# serv_open8_sotb.net
KiCad netlist of a schematic drawn in EAGLE
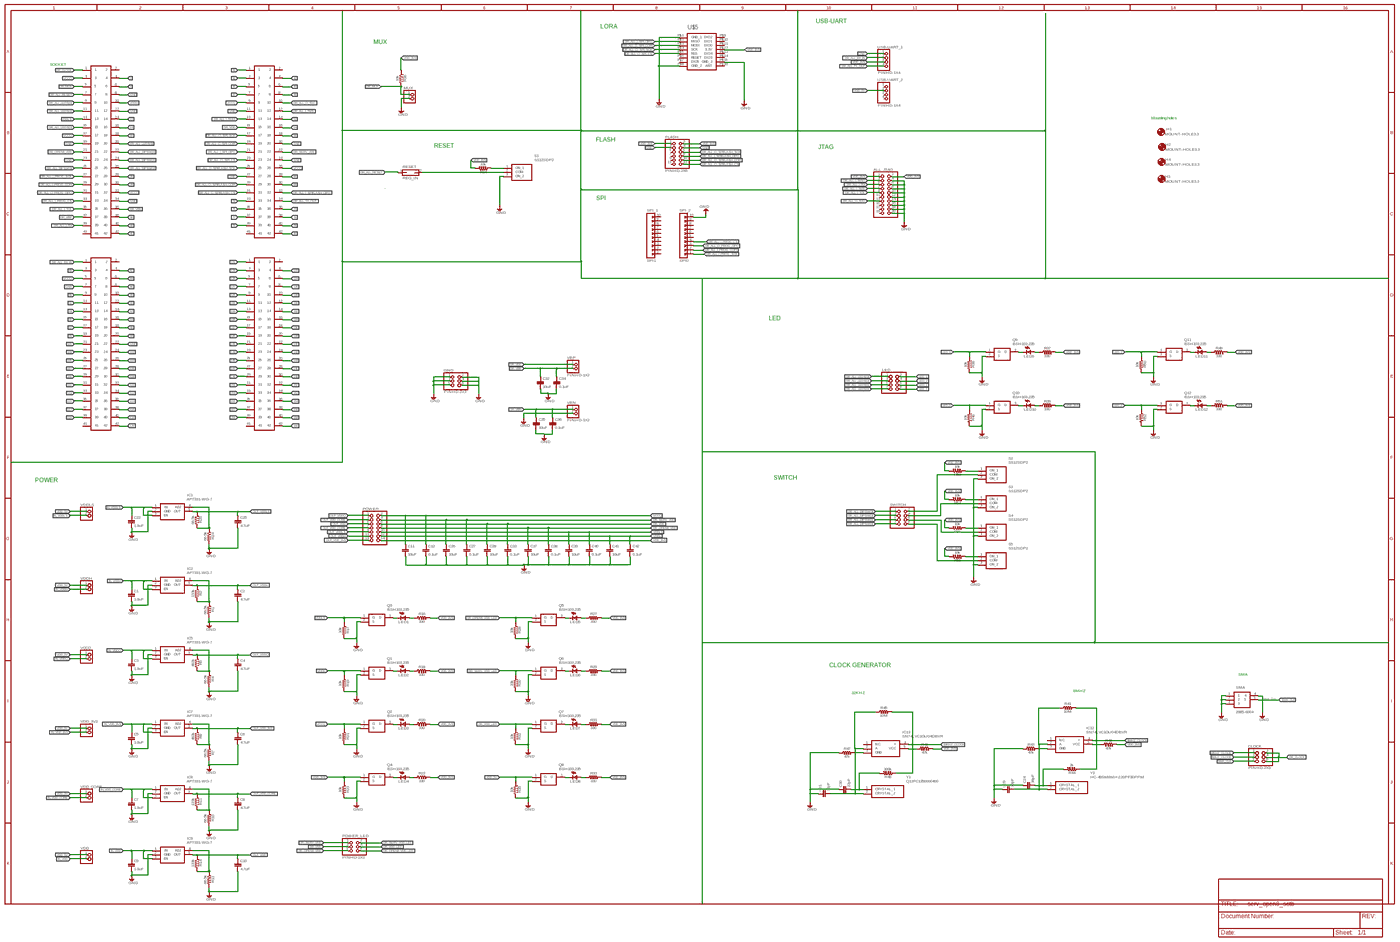
[diagram p0: schematic, sheet 1, overview]
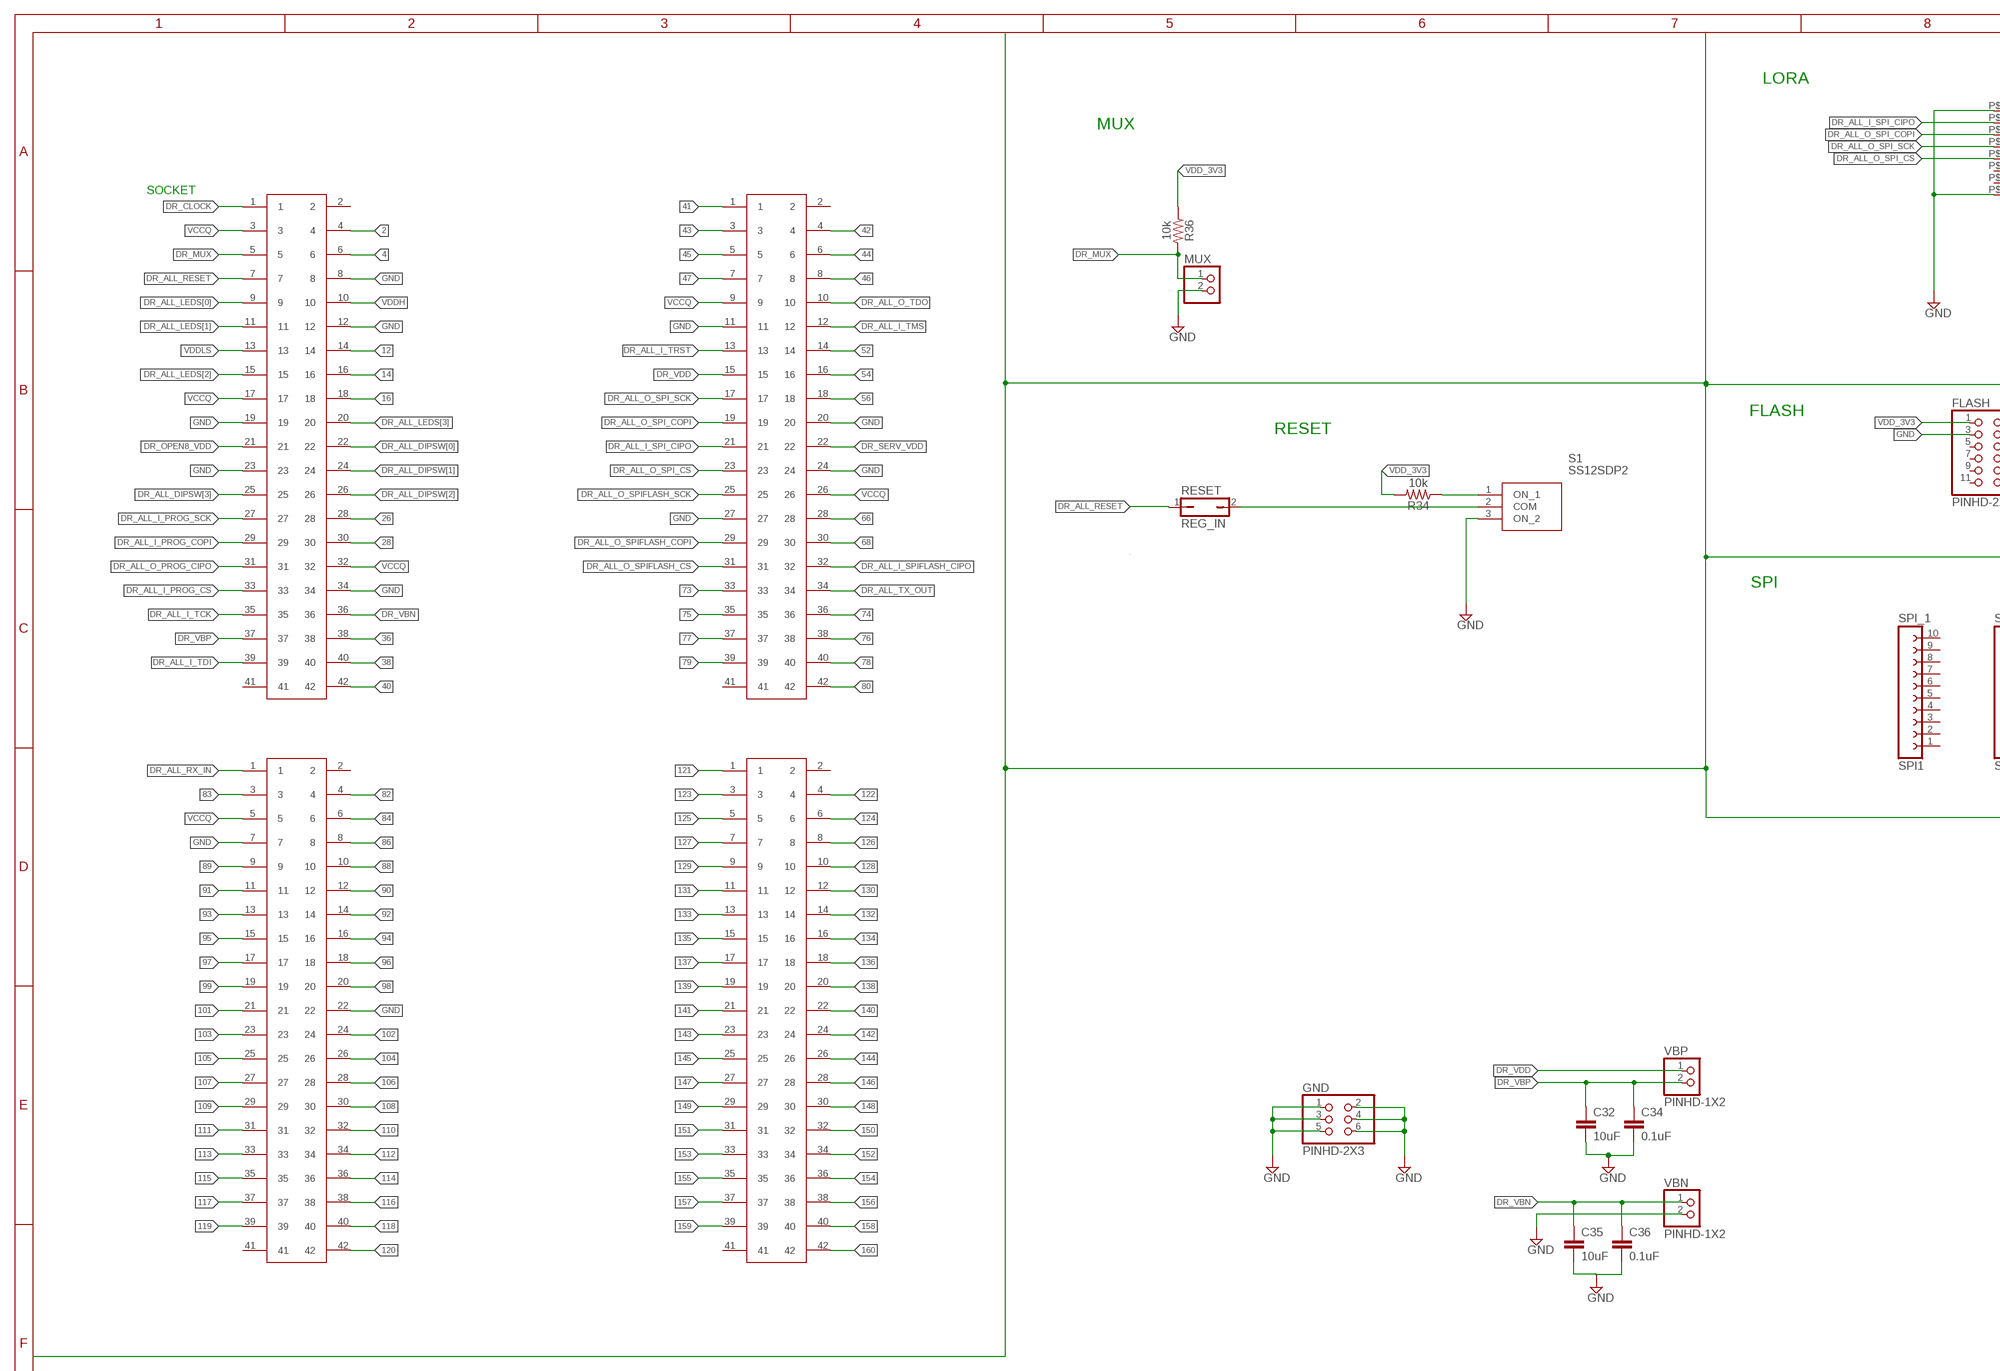
[diagram p1: schematic, sheet 1, part 1 of 4]
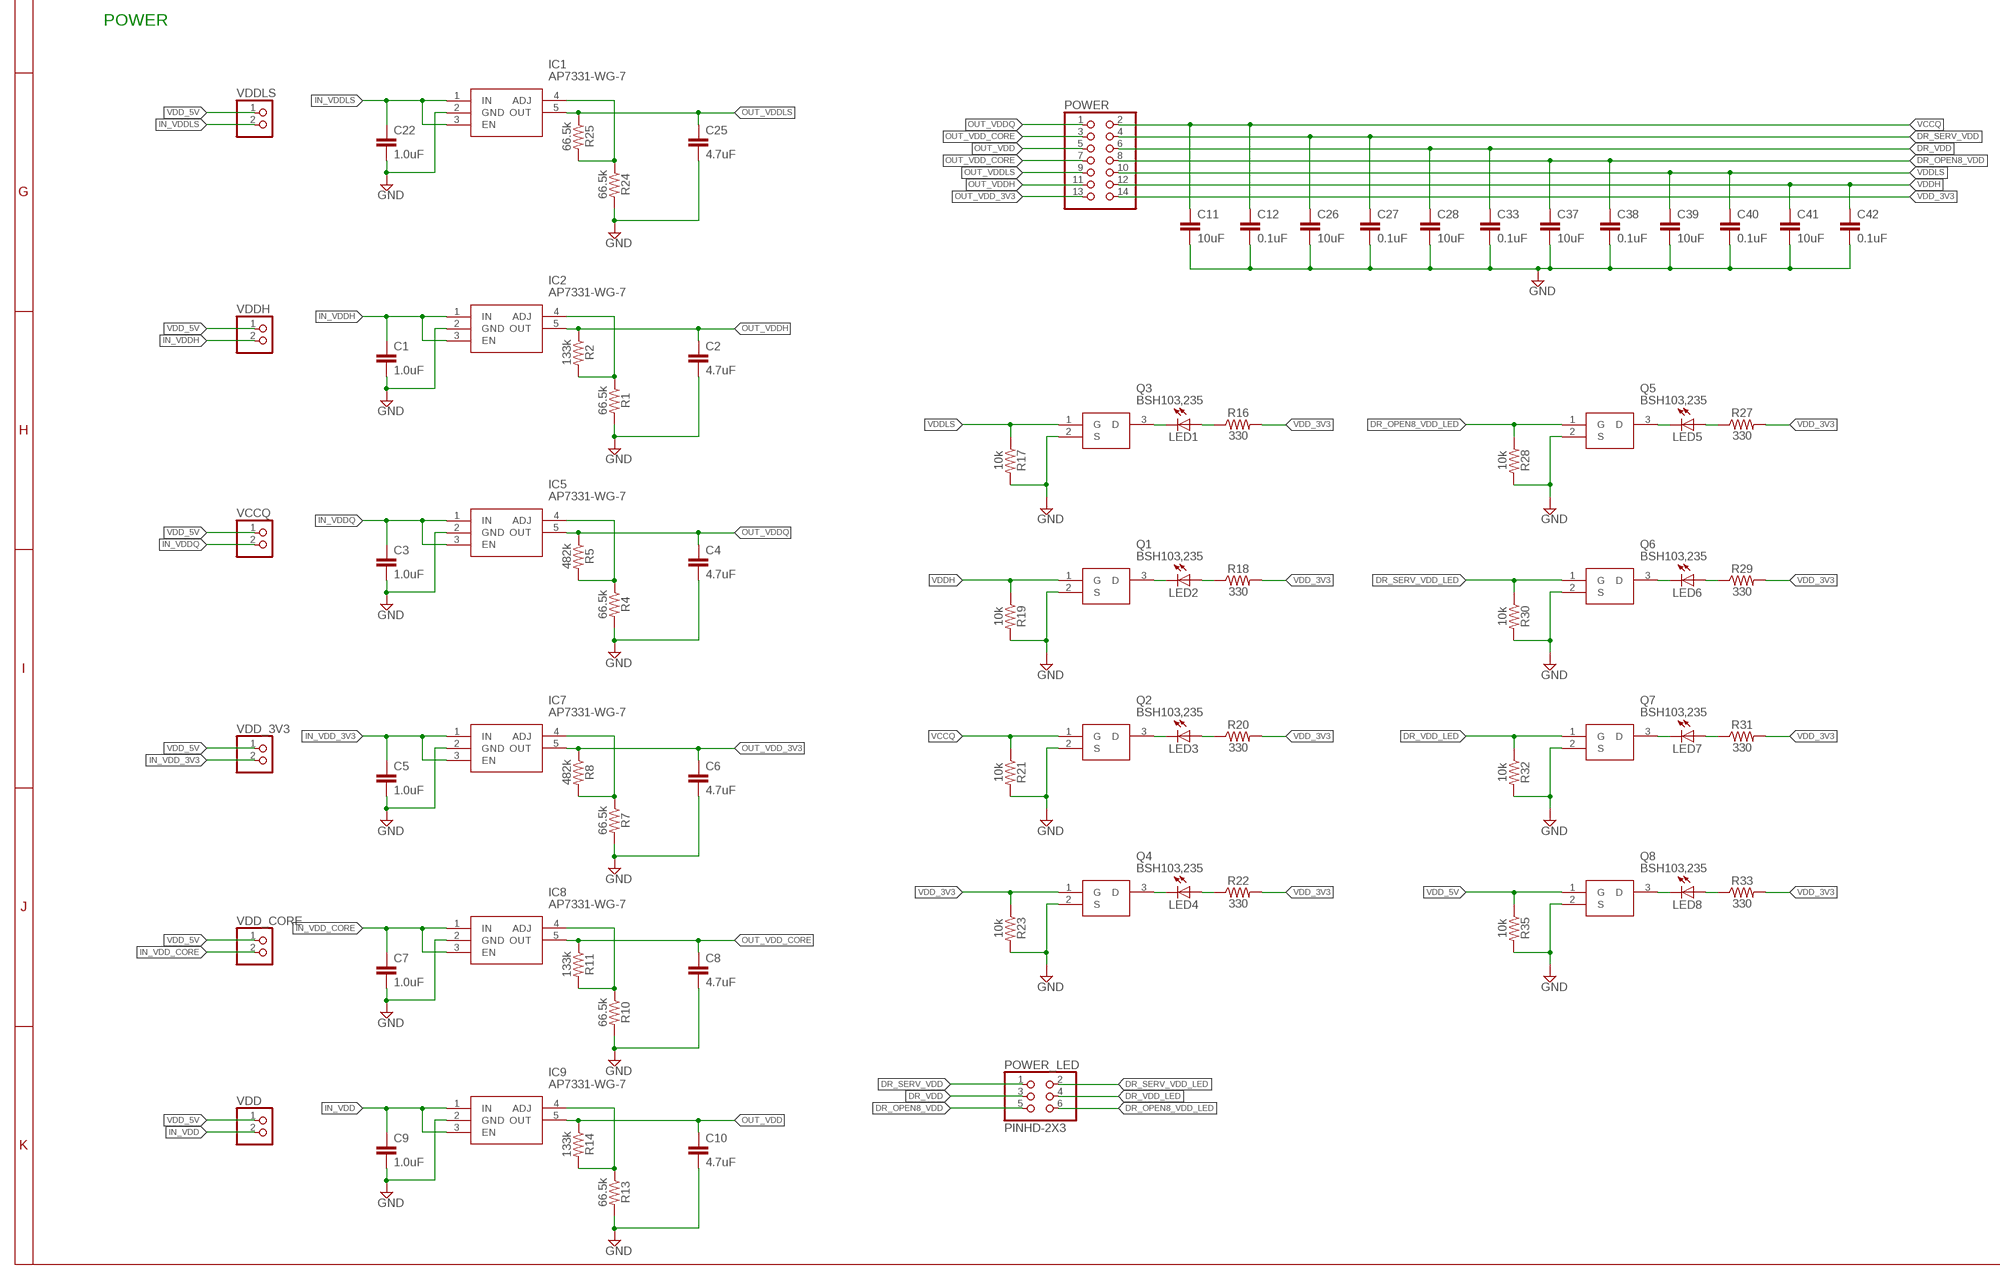
[diagram p2: schematic, sheet 1, part 2 of 4]
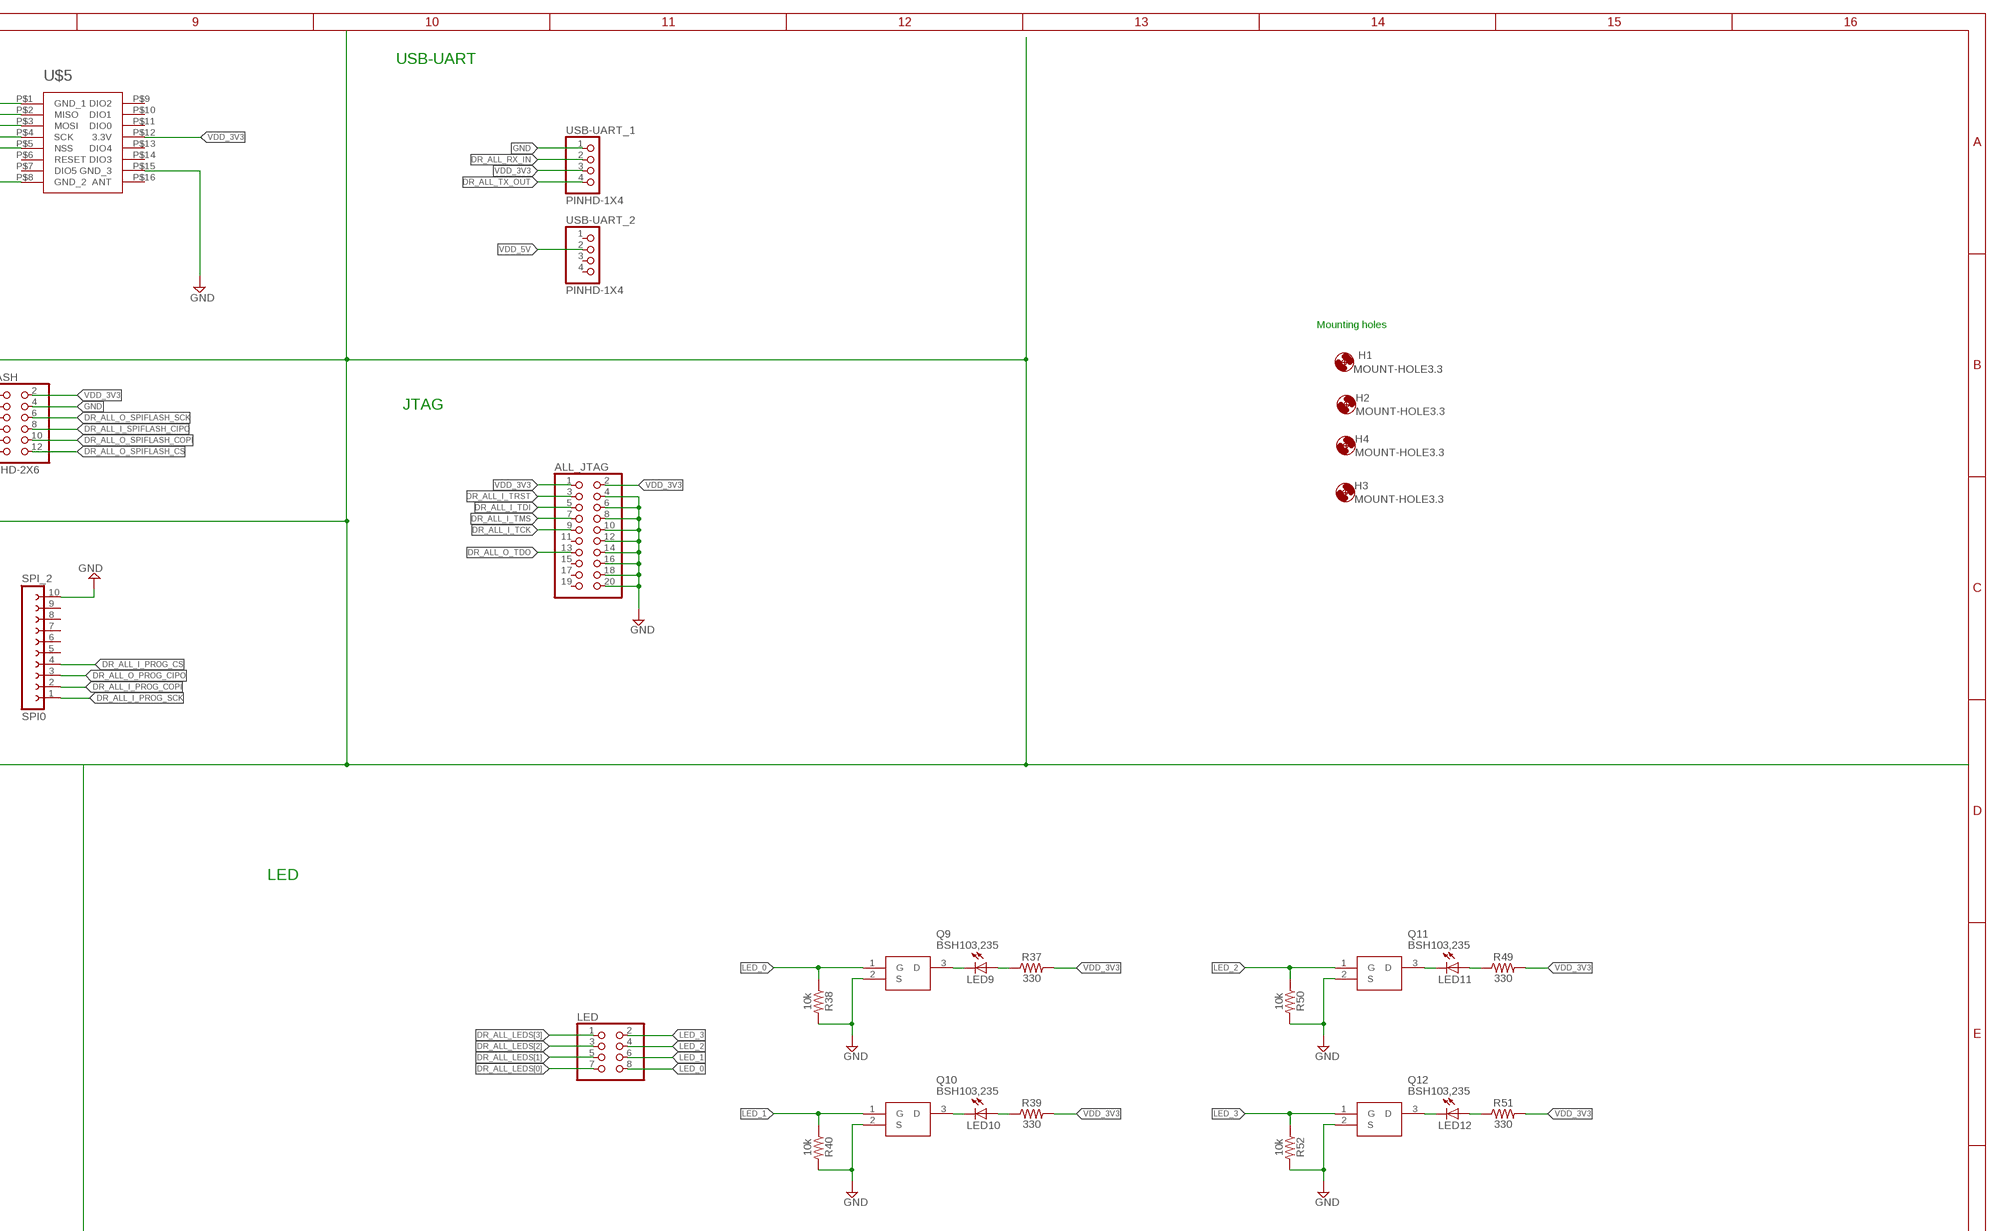
[diagram p3: schematic, sheet 1, part 3 of 4]
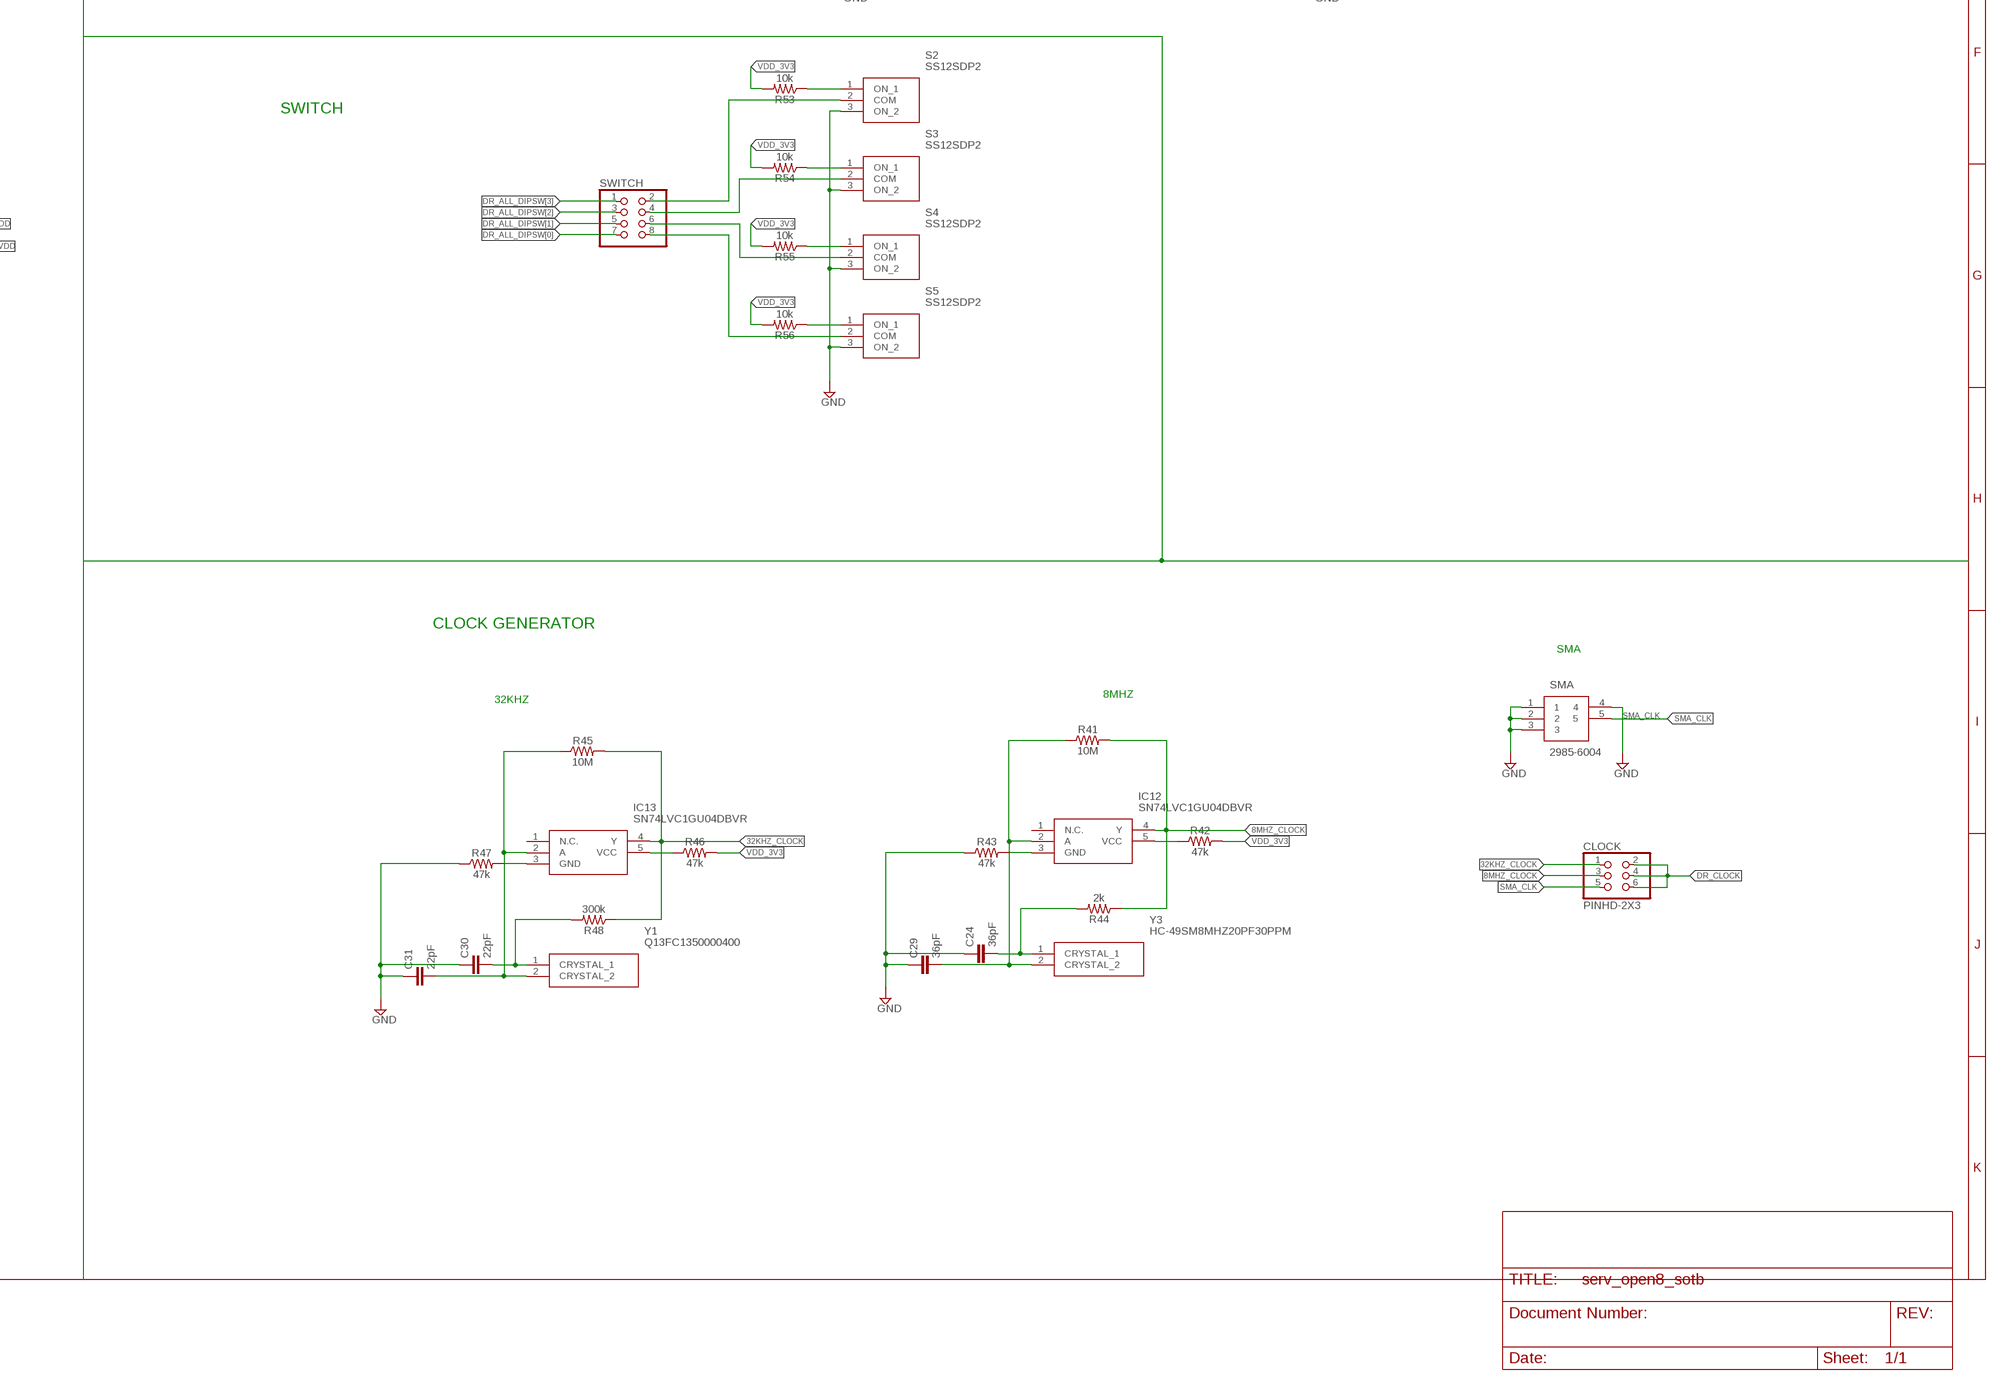
[diagram p4: schematic, sheet 1, part 4 of 4]

(export (version "E")
  (design (tool "Eeschema 10.0.6"))
  (components
    (comp (ref "ALL_JTAG")
      (value "PINHD-2X10")
      (footprint "eagle-import:2X10")
      (libsource (lib "eagle-import") (part "PINHD-2X10"))
    )
    (comp (ref "C1")
      (value "1.0uF")
      (footprint "eagle-import:0805")
      (libsource (lib "eagle-import") (part "1.0UF-0805-25V-(+80/-20%)"))
    )
    (comp (ref "C2")
      (value "4.7uF")
      (footprint "eagle-import:0805")
      (libsource (lib "eagle-import") (part "1.0UF-0805-25V-(+80/-20%)"))
    )
    (comp (ref "C3")
      (value "1.0uF")
      (footprint "eagle-import:0805")
      (libsource (lib "eagle-import") (part "1.0UF-0805-25V-(+80/-20%)"))
    )
    (comp (ref "C4")
      (value "4.7uF")
      (footprint "eagle-import:0805")
      (libsource (lib "eagle-import") (part "1.0UF-0805-25V-(+80/-20%)"))
    )
    (comp (ref "C5")
      (value "1.0uF")
      (footprint "eagle-import:0805")
      (libsource (lib "eagle-import") (part "1.0UF-0805-25V-(+80/-20%)"))
    )
    (comp (ref "C6")
      (value "4.7uF")
      (footprint "eagle-import:0805")
      (libsource (lib "eagle-import") (part "1.0UF-0805-25V-(+80/-20%)"))
    )
    (comp (ref "C7")
      (value "1.0uF")
      (footprint "eagle-import:0805")
      (libsource (lib "eagle-import") (part "1.0UF-0805-25V-(+80/-20%)"))
    )
    (comp (ref "C8")
      (value "4.7uF")
      (footprint "eagle-import:0805")
      (libsource (lib "eagle-import") (part "1.0UF-0805-25V-(+80/-20%)"))
    )
    (comp (ref "C9")
      (value "1.0uF")
      (footprint "eagle-import:0805")
      (libsource (lib "eagle-import") (part "1.0UF-0805-25V-(+80/-20%)"))
    )
    (comp (ref "C10")
      (value "4.7uF")
      (footprint "eagle-import:0805")
      (libsource (lib "eagle-import") (part "1.0UF-0805-25V-(+80/-20%)"))
    )
    (comp (ref "C11")
      (value "10uF")
      (footprint "eagle-import:0805")
      (libsource (lib "eagle-import") (part "1.0UF-0805-25V-(+80/-20%)"))
    )
    (comp (ref "C12")
      (value "0.1uF")
      (footprint "eagle-import:0805")
      (libsource (lib "eagle-import") (part "1.0UF-0805-25V-(+80/-20%)"))
    )
    (comp (ref "C22")
      (value "1.0uF")
      (footprint "eagle-import:0805")
      (libsource (lib "eagle-import") (part "1.0UF-0805-25V-(+80/-20%)"))
    )
    (comp (ref "C24")
      (value "36pF")
      (footprint "eagle-import:0805")
      (libsource (lib "eagle-import") (part "1.0UF-0805-25V-(+80/-20%)"))
    )
    (comp (ref "C25")
      (value "4.7uF")
      (footprint "eagle-import:0805")
      (libsource (lib "eagle-import") (part "1.0UF-0805-25V-(+80/-20%)"))
    )
    (comp (ref "C26")
      (value "10uF")
      (footprint "eagle-import:0805")
      (libsource (lib "eagle-import") (part "1.0UF-0805-25V-(+80/-20%)"))
    )
    (comp (ref "C27")
      (value "0.1uF")
      (footprint "eagle-import:0805")
      (libsource (lib "eagle-import") (part "1.0UF-0805-25V-(+80/-20%)"))
    )
    (comp (ref "C28")
      (value "10uF")
      (footprint "eagle-import:0805")
      (libsource (lib "eagle-import") (part "1.0UF-0805-25V-(+80/-20%)"))
    )
    (comp (ref "C29")
      (value "36pF")
      (footprint "eagle-import:0805")
      (libsource (lib "eagle-import") (part "1.0UF-0805-25V-(+80/-20%)"))
    )
    (comp (ref "C30")
      (value "22pF")
      (footprint "eagle-import:0805")
      (libsource (lib "eagle-import") (part "1.0UF-0805-25V-(+80/-20%)"))
    )
    (comp (ref "C31")
      (value "22pF")
      (footprint "eagle-import:0805")
      (libsource (lib "eagle-import") (part "1.0UF-0805-25V-(+80/-20%)"))
    )
    (comp (ref "C32")
      (value "10uF")
      (footprint "eagle-import:0805")
      (libsource (lib "eagle-import") (part "1.0UF-0805-25V-(+80/-20%)"))
    )
    (comp (ref "C33")
      (value "0.1uF")
      (footprint "eagle-import:0805")
      (libsource (lib "eagle-import") (part "1.0UF-0805-25V-(+80/-20%)"))
    )
    (comp (ref "C34")
      (value "0.1uF")
      (footprint "eagle-import:0805")
      (libsource (lib "eagle-import") (part "1.0UF-0805-25V-(+80/-20%)"))
    )
    (comp (ref "C35")
      (value "10uF")
      (footprint "eagle-import:0805")
      (libsource (lib "eagle-import") (part "1.0UF-0805-25V-(+80/-20%)"))
    )
    (comp (ref "C36")
      (value "0.1uF")
      (footprint "eagle-import:0805")
      (libsource (lib "eagle-import") (part "1.0UF-0805-25V-(+80/-20%)"))
    )
    (comp (ref "C37")
      (value "10uF")
      (footprint "eagle-import:0805")
      (libsource (lib "eagle-import") (part "1.0UF-0805-25V-(+80/-20%)"))
    )
    (comp (ref "C38")
      (value "0.1uF")
      (footprint "eagle-import:0805")
      (libsource (lib "eagle-import") (part "1.0UF-0805-25V-(+80/-20%)"))
    )
    (comp (ref "C39")
      (value "10uF")
      (footprint "eagle-import:0805")
      (libsource (lib "eagle-import") (part "1.0UF-0805-25V-(+80/-20%)"))
    )
    (comp (ref "C40")
      (value "0.1uF")
      (footprint "eagle-import:0805")
      (libsource (lib "eagle-import") (part "1.0UF-0805-25V-(+80/-20%)"))
    )
    (comp (ref "C41")
      (value "10uF")
      (footprint "eagle-import:0805")
      (libsource (lib "eagle-import") (part "1.0UF-0805-25V-(+80/-20%)"))
    )
    (comp (ref "C42")
      (value "0.1uF")
      (footprint "eagle-import:0805")
      (libsource (lib "eagle-import") (part "1.0UF-0805-25V-(+80/-20%)"))
    )
    (comp (ref "CLOCK")
      (value "PINHD-2X3")
      (footprint "eagle-import:2X03")
      (libsource (lib "eagle-import") (part "PINHD-2X3"))
    )
    (comp (ref "FLASH")
      (value "PINHD-2X6")
      (footprint "eagle-import:2X06")
      (libsource (lib "eagle-import") (part "PINHD-2X6"))
    )
    (comp (ref "GND")
      (value "PINHD-2X3")
      (footprint "eagle-import:2X03")
      (libsource (lib "eagle-import") (part "PINHD-2X3"))
    )
    (comp (ref "H1")
      (value "MOUNT-HOLE3.3")
      (footprint "eagle-import:3,3")
      (libsource (lib "eagle-import") (part "MOUNT-HOLE3.3"))
    )
    (comp (ref "H2")
      (value "MOUNT-HOLE3.3")
      (footprint "eagle-import:3,3")
      (libsource (lib "eagle-import") (part "MOUNT-HOLE3.3"))
    )
    (comp (ref "H3")
      (value "MOUNT-HOLE3.3")
      (footprint "eagle-import:3,3")
      (libsource (lib "eagle-import") (part "MOUNT-HOLE3.3"))
    )
    (comp (ref "H4")
      (value "MOUNT-HOLE3.3")
      (footprint "eagle-import:3,3")
      (libsource (lib "eagle-import") (part "MOUNT-HOLE3.3"))
    )
    (comp (ref "IC1")
      (value "AP7331-WG-7")
      (footprint "eagle-import:SOT95P285X145-5N")
      (fields (field (name "MOUSER_PART_NUMBER") "621-AP7331-WG-7"))
      (libsource (lib "eagle-import") (part "AP7331-WG-7"))
    )
    (comp (ref "IC2")
      (value "AP7331-WG-7")
      (footprint "eagle-import:SOT95P285X145-5N")
      (fields (field (name "MOUSER_PART_NUMBER") "621-AP7331-WG-7"))
      (libsource (lib "eagle-import") (part "AP7331-WG-7"))
    )
    (comp (ref "IC5")
      (value "AP7331-WG-7")
      (footprint "eagle-import:SOT95P285X145-5N")
      (fields (field (name "MOUSER_PART_NUMBER") "621-AP7331-WG-7"))
      (libsource (lib "eagle-import") (part "AP7331-WG-7"))
    )
    (comp (ref "IC7")
      (value "AP7331-WG-7")
      (footprint "eagle-import:SOT95P285X145-5N")
      (fields (field (name "MOUSER_PART_NUMBER") "621-AP7331-WG-7"))
      (libsource (lib "eagle-import") (part "AP7331-WG-7"))
    )
    (comp (ref "IC8")
      (value "AP7331-WG-7")
      (footprint "eagle-import:SOT95P285X145-5N")
      (fields (field (name "MOUSER_PART_NUMBER") "621-AP7331-WG-7"))
      (libsource (lib "eagle-import") (part "AP7331-WG-7"))
    )
    (comp (ref "IC9")
      (value "AP7331-WG-7")
      (footprint "eagle-import:SOT95P285X145-5N")
      (fields (field (name "MOUSER_PART_NUMBER") "621-AP7331-WG-7"))
      (libsource (lib "eagle-import") (part "AP7331-WG-7"))
    )
    (comp (ref "IC12")
      (value "SN74LVC1GU04DBVR")
      (footprint "eagle-import:SOT95P280X145-5N")
      (fields (field (name "MOUSER_PART_NUMBER") "595-SN74LVC1GU04DBVR"))
      (libsource (lib "eagle-import") (part "SN74LVC1GU04DBVR"))
    )
    (comp (ref "IC13")
      (value "SN74LVC1GU04DBVR")
      (footprint "eagle-import:SOT95P280X145-5N")
      (fields (field (name "MOUSER_PART_NUMBER") "595-SN74LVC1GU04DBVR"))
      (libsource (lib "eagle-import") (part "SN74LVC1GU04DBVR"))
    )
    (comp (ref "LED")
      (value "PINHD-2X4")
      (footprint "eagle-import:2X04")
      (libsource (lib "eagle-import") (part "PINHD-2X4"))
    )
    (comp (ref "LED1")
      (value "LEDCHIP-LED0805")
      (footprint "eagle-import:CHIP-LED0805")
      (libsource (lib "eagle-import") (part "LEDCHIP-LED0805"))
    )
    (comp (ref "LED2")
      (value "LEDCHIP-LED0805")
      (footprint "eagle-import:CHIP-LED0805")
      (libsource (lib "eagle-import") (part "LEDCHIP-LED0805"))
    )
    (comp (ref "LED3")
      (value "LEDCHIP-LED0805")
      (footprint "eagle-import:CHIP-LED0805")
      (libsource (lib "eagle-import") (part "LEDCHIP-LED0805"))
    )
    (comp (ref "LED4")
      (value "LEDCHIP-LED0805")
      (footprint "eagle-import:CHIP-LED0805")
      (libsource (lib "eagle-import") (part "LEDCHIP-LED0805"))
    )
    (comp (ref "LED5")
      (value "LEDCHIP-LED0805")
      (footprint "eagle-import:CHIP-LED0805")
      (libsource (lib "eagle-import") (part "LEDCHIP-LED0805"))
    )
    (comp (ref "LED6")
      (value "LEDCHIP-LED0805")
      (footprint "eagle-import:CHIP-LED0805")
      (libsource (lib "eagle-import") (part "LEDCHIP-LED0805"))
    )
    (comp (ref "LED7")
      (value "LEDCHIP-LED0805")
      (footprint "eagle-import:CHIP-LED0805")
      (libsource (lib "eagle-import") (part "LEDCHIP-LED0805"))
    )
    (comp (ref "LED8")
      (value "LEDCHIP-LED0805")
      (footprint "eagle-import:CHIP-LED0805")
      (libsource (lib "eagle-import") (part "LEDCHIP-LED0805"))
    )
    (comp (ref "LED9")
      (value "LEDCHIP-LED0805")
      (footprint "eagle-import:CHIP-LED0805")
      (libsource (lib "eagle-import") (part "LEDCHIP-LED0805"))
    )
    (comp (ref "LED10")
      (value "LEDCHIP-LED0805")
      (footprint "eagle-import:CHIP-LED0805")
      (libsource (lib "eagle-import") (part "LEDCHIP-LED0805"))
    )
    (comp (ref "LED11")
      (value "LEDCHIP-LED0805")
      (footprint "eagle-import:CHIP-LED0805")
      (libsource (lib "eagle-import") (part "LEDCHIP-LED0805"))
    )
    (comp (ref "LED12")
      (value "LEDCHIP-LED0805")
      (footprint "eagle-import:CHIP-LED0805")
      (libsource (lib "eagle-import") (part "LEDCHIP-LED0805"))
    )
    (comp (ref "MUX")
      (value "PINHD-1X2")
      (footprint "eagle-import:1X02")
      (libsource (lib "eagle-import") (part "pinhead_325_PINHD-1X2"))
    )
    (comp (ref "POWER")
      (value "PINHD-2X7")
      (footprint "eagle-import:2X07")
      (libsource (lib "eagle-import") (part "PINHD-2X7"))
    )
    (comp (ref "POWER_LED")
      (value "PINHD-2X3")
      (footprint "eagle-import:2X03")
      (libsource (lib "eagle-import") (part "PINHD-2X3"))
    )
    (comp (ref "Q1")
      (value "BSH103,235")
      (footprint "eagle-import:SOT95P230X110-3N")
      (fields (field (name "MOUSER_PART_NUMBER") "771-BSH103235"))
      (libsource (lib "eagle-import") (part "BSH103,235"))
    )
    (comp (ref "Q2")
      (value "BSH103,235")
      (footprint "eagle-import:SOT95P230X110-3N")
      (fields (field (name "MOUSER_PART_NUMBER") "771-BSH103235"))
      (libsource (lib "eagle-import") (part "BSH103,235"))
    )
    (comp (ref "Q3")
      (value "BSH103,235")
      (footprint "eagle-import:SOT95P230X110-3N")
      (fields (field (name "MOUSER_PART_NUMBER") "771-BSH103235"))
      (libsource (lib "eagle-import") (part "BSH103,235"))
    )
    (comp (ref "Q4")
      (value "BSH103,235")
      (footprint "eagle-import:SOT95P230X110-3N")
      (fields (field (name "MOUSER_PART_NUMBER") "771-BSH103235"))
      (libsource (lib "eagle-import") (part "BSH103,235"))
    )
    (comp (ref "Q5")
      (value "BSH103,235")
      (footprint "eagle-import:SOT95P230X110-3N")
      (fields (field (name "MOUSER_PART_NUMBER") "771-BSH103235"))
      (libsource (lib "eagle-import") (part "BSH103,235"))
    )
    (comp (ref "Q6")
      (value "BSH103,235")
      (footprint "eagle-import:SOT95P230X110-3N")
      (fields (field (name "MOUSER_PART_NUMBER") "771-BSH103235"))
      (libsource (lib "eagle-import") (part "BSH103,235"))
    )
    (comp (ref "Q7")
      (value "BSH103,235")
      (footprint "eagle-import:SOT95P230X110-3N")
      (fields (field (name "MOUSER_PART_NUMBER") "771-BSH103235"))
      (libsource (lib "eagle-import") (part "BSH103,235"))
    )
    (comp (ref "Q8")
      (value "BSH103,235")
      (footprint "eagle-import:SOT95P230X110-3N")
      (fields (field (name "MOUSER_PART_NUMBER") "771-BSH103235"))
      (libsource (lib "eagle-import") (part "BSH103,235"))
    )
    (comp (ref "Q9")
      (value "BSH103,235")
      (footprint "eagle-import:SOT95P230X110-3N")
      (fields (field (name "MOUSER_PART_NUMBER") "771-BSH103235"))
      (libsource (lib "eagle-import") (part "BSH103,235"))
    )
    (comp (ref "Q10")
      (value "BSH103,235")
      (footprint "eagle-import:SOT95P230X110-3N")
      (fields (field (name "MOUSER_PART_NUMBER") "771-BSH103235"))
      (libsource (lib "eagle-import") (part "BSH103,235"))
    )
    (comp (ref "Q11")
      (value "BSH103,235")
      (footprint "eagle-import:SOT95P230X110-3N")
      (fields (field (name "MOUSER_PART_NUMBER") "771-BSH103235"))
      (libsource (lib "eagle-import") (part "BSH103,235"))
    )
    (comp (ref "Q12")
      (value "BSH103,235")
      (footprint "eagle-import:SOT95P230X110-3N")
      (fields (field (name "MOUSER_PART_NUMBER") "771-BSH103235"))
      (libsource (lib "eagle-import") (part "BSH103,235"))
    )
    (comp (ref "R1")
      (value "66.5k")
      (footprint "eagle-import:0805")
      (libsource (lib "eagle-import") (part "0.3OHM-0805-1/8W-1%"))
    )
    (comp (ref "R2")
      (value "133k")
      (footprint "eagle-import:0805")
      (libsource (lib "eagle-import") (part "0.3OHM-0805-1/8W-1%"))
    )
    (comp (ref "R4")
      (value "66.5k")
      (footprint "eagle-import:0805")
      (libsource (lib "eagle-import") (part "0.3OHM-0805-1/8W-1%"))
    )
    (comp (ref "R5")
      (value "482k")
      (footprint "eagle-import:0805")
      (libsource (lib "eagle-import") (part "0.3OHM-0805-1/8W-1%"))
    )
    (comp (ref "R7")
      (value "66.5k")
      (footprint "eagle-import:0805")
      (libsource (lib "eagle-import") (part "0.3OHM-0805-1/8W-1%"))
    )
    (comp (ref "R8")
      (value "482k")
      (footprint "eagle-import:0805")
      (libsource (lib "eagle-import") (part "0.3OHM-0805-1/8W-1%"))
    )
    (comp (ref "R10")
      (value "66.5k")
      (footprint "eagle-import:0805")
      (libsource (lib "eagle-import") (part "0.3OHM-0805-1/8W-1%"))
    )
    (comp (ref "R11")
      (value "133k")
      (footprint "eagle-import:0805")
      (libsource (lib "eagle-import") (part "0.3OHM-0805-1/8W-1%"))
    )
    (comp (ref "R13")
      (value "66.5k")
      (footprint "eagle-import:0805")
      (libsource (lib "eagle-import") (part "0.3OHM-0805-1/8W-1%"))
    )
    (comp (ref "R14")
      (value "133k")
      (footprint "eagle-import:0805")
      (libsource (lib "eagle-import") (part "0.3OHM-0805-1/8W-1%"))
    )
    (comp (ref "R16")
      (value "330")
      (footprint "eagle-import:0805")
      (libsource (lib "eagle-import") (part "0.3OHM-0805-1/8W-1%"))
    )
    (comp (ref "R17")
      (value "10k")
      (footprint "eagle-import:0805")
      (libsource (lib "eagle-import") (part "0.3OHM-0805-1/8W-1%"))
    )
    (comp (ref "R18")
      (value "330")
      (footprint "eagle-import:0805")
      (libsource (lib "eagle-import") (part "0.3OHM-0805-1/8W-1%"))
    )
    (comp (ref "R19")
      (value "10k")
      (footprint "eagle-import:0805")
      (libsource (lib "eagle-import") (part "0.3OHM-0805-1/8W-1%"))
    )
    (comp (ref "R20")
      (value "330")
      (footprint "eagle-import:0805")
      (libsource (lib "eagle-import") (part "0.3OHM-0805-1/8W-1%"))
    )
    (comp (ref "R21")
      (value "10k")
      (footprint "eagle-import:0805")
      (libsource (lib "eagle-import") (part "0.3OHM-0805-1/8W-1%"))
    )
    (comp (ref "R22")
      (value "330")
      (footprint "eagle-import:0805")
      (libsource (lib "eagle-import") (part "0.3OHM-0805-1/8W-1%"))
    )
    (comp (ref "R23")
      (value "10k")
      (footprint "eagle-import:0805")
      (libsource (lib "eagle-import") (part "0.3OHM-0805-1/8W-1%"))
    )
    (comp (ref "R24")
      (value "66.5k")
      (footprint "eagle-import:0805")
      (libsource (lib "eagle-import") (part "0.3OHM-0805-1/8W-1%"))
    )
    (comp (ref "R25")
      (value "66.5k")
      (footprint "eagle-import:0805")
      (libsource (lib "eagle-import") (part "0.3OHM-0805-1/8W-1%"))
    )
    (comp (ref "R27")
      (value "330")
      (footprint "eagle-import:0805")
      (libsource (lib "eagle-import") (part "0.3OHM-0805-1/8W-1%"))
    )
    (comp (ref "R28")
      (value "10k")
      (footprint "eagle-import:0805")
      (libsource (lib "eagle-import") (part "0.3OHM-0805-1/8W-1%"))
    )
    (comp (ref "R29")
      (value "330")
      (footprint "eagle-import:0805")
      (libsource (lib "eagle-import") (part "0.3OHM-0805-1/8W-1%"))
    )
    (comp (ref "R30")
      (value "10k")
      (footprint "eagle-import:0805")
      (libsource (lib "eagle-import") (part "0.3OHM-0805-1/8W-1%"))
    )
    (comp (ref "R31")
      (value "330")
      (footprint "eagle-import:0805")
      (libsource (lib "eagle-import") (part "0.3OHM-0805-1/8W-1%"))
    )
    (comp (ref "R32")
      (value "10k")
      (footprint "eagle-import:0805")
      (libsource (lib "eagle-import") (part "0.3OHM-0805-1/8W-1%"))
    )
    (comp (ref "R33")
      (value "330")
      (footprint "eagle-import:0805")
      (libsource (lib "eagle-import") (part "0.3OHM-0805-1/8W-1%"))
    )
    (comp (ref "R34")
      (value "10k")
      (footprint "eagle-import:0805")
      (libsource (lib "eagle-import") (part "0.3OHM-0805-1/8W-1%"))
    )
    (comp (ref "R35")
      (value "10k")
      (footprint "eagle-import:0805")
      (libsource (lib "eagle-import") (part "0.3OHM-0805-1/8W-1%"))
    )
    (comp (ref "R36")
      (value "10k")
      (footprint "eagle-import:0805")
      (libsource (lib "eagle-import") (part "0.3OHM-0805-1/8W-1%"))
    )
    (comp (ref "R37")
      (value "330")
      (footprint "eagle-import:0805")
      (libsource (lib "eagle-import") (part "0.3OHM-0805-1/8W-1%"))
    )
    (comp (ref "R38")
      (value "10k")
      (footprint "eagle-import:0805")
      (libsource (lib "eagle-import") (part "0.3OHM-0805-1/8W-1%"))
    )
    (comp (ref "R39")
      (value "330")
      (footprint "eagle-import:0805")
      (libsource (lib "eagle-import") (part "0.3OHM-0805-1/8W-1%"))
    )
    (comp (ref "R40")
      (value "10k")
      (footprint "eagle-import:0805")
      (libsource (lib "eagle-import") (part "0.3OHM-0805-1/8W-1%"))
    )
    (comp (ref "R41")
      (value "10M")
      (footprint "eagle-import:0805")
      (libsource (lib "eagle-import") (part "0.3OHM-0805-1/8W-1%"))
    )
    (comp (ref "R42")
      (value "47k")
      (footprint "eagle-import:0805")
      (libsource (lib "eagle-import") (part "0.3OHM-0805-1/8W-1%"))
    )
    (comp (ref "R43")
      (value "47k")
      (footprint "eagle-import:0805")
      (libsource (lib "eagle-import") (part "0.3OHM-0805-1/8W-1%"))
    )
    (comp (ref "R44")
      (value "2k")
      (footprint "eagle-import:0805")
      (libsource (lib "eagle-import") (part "0.3OHM-0805-1/8W-1%"))
    )
    (comp (ref "R45")
      (value "10M")
      (footprint "eagle-import:0805")
      (libsource (lib "eagle-import") (part "0.3OHM-0805-1/8W-1%"))
    )
    (comp (ref "R46")
      (value "47k")
      (footprint "eagle-import:0805")
      (libsource (lib "eagle-import") (part "0.3OHM-0805-1/8W-1%"))
    )
    (comp (ref "R47")
      (value "47k")
      (footprint "eagle-import:0805")
      (libsource (lib "eagle-import") (part "0.3OHM-0805-1/8W-1%"))
    )
    (comp (ref "R48")
      (value "300k")
      (footprint "eagle-import:0805")
      (libsource (lib "eagle-import") (part "0.3OHM-0805-1/8W-1%"))
    )
    (comp (ref "R49")
      (value "330")
      (footprint "eagle-import:0805")
      (libsource (lib "eagle-import") (part "0.3OHM-0805-1/8W-1%"))
    )
    (comp (ref "R50")
      (value "10k")
      (footprint "eagle-import:0805")
      (libsource (lib "eagle-import") (part "0.3OHM-0805-1/8W-1%"))
    )
    (comp (ref "R51")
      (value "330")
      (footprint "eagle-import:0805")
      (libsource (lib "eagle-import") (part "0.3OHM-0805-1/8W-1%"))
    )
    (comp (ref "R52")
      (value "10k")
      (footprint "eagle-import:0805")
      (libsource (lib "eagle-import") (part "0.3OHM-0805-1/8W-1%"))
    )
    (comp (ref "R53")
      (value "10k")
      (footprint "eagle-import:0805")
      (libsource (lib "eagle-import") (part "0.3OHM-0805-1/8W-1%"))
    )
    (comp (ref "R54")
      (value "10k")
      (footprint "eagle-import:0805")
      (libsource (lib "eagle-import") (part "0.3OHM-0805-1/8W-1%"))
    )
    (comp (ref "R55")
      (value "10k")
      (footprint "eagle-import:0805")
      (libsource (lib "eagle-import") (part "0.3OHM-0805-1/8W-1%"))
    )
    (comp (ref "R56")
      (value "10k")
      (footprint "eagle-import:0805")
      (libsource (lib "eagle-import") (part "0.3OHM-0805-1/8W-1%"))
    )
    (comp (ref "RESET")
      (value "REG_IN")
      (footprint "eagle-import:JP1")
      (libsource (lib "eagle-import") (part "JP1Q"))
    )
    (comp (ref "S1")
      (value "SS12SDP2")
      (footprint "eagle-import:SS12SDP2")
      (fields (field (name "MOUSER_PART_NUMBER") "633-SS12SDP2"))
      (libsource (lib "eagle-import") (part "SS12SDP2"))
    )
    (comp (ref "S2")
      (value "SS12SDP2")
      (footprint "eagle-import:SS12SDP2")
      (fields (field (name "MOUSER_PART_NUMBER") "633-SS12SDP2"))
      (libsource (lib "eagle-import") (part "SS12SDP2"))
    )
    (comp (ref "S3")
      (value "SS12SDP2")
      (footprint "eagle-import:SS12SDP2")
      (fields (field (name "MOUSER_PART_NUMBER") "633-SS12SDP2"))
      (libsource (lib "eagle-import") (part "SS12SDP2"))
    )
    (comp (ref "S4")
      (value "SS12SDP2")
      (footprint "eagle-import:SS12SDP2")
      (fields (field (name "MOUSER_PART_NUMBER") "633-SS12SDP2"))
      (libsource (lib "eagle-import") (part "SS12SDP2"))
    )
    (comp (ref "S5")
      (value "SS12SDP2")
      (footprint "eagle-import:SS12SDP2")
      (fields (field (name "MOUSER_PART_NUMBER") "633-SS12SDP2"))
      (libsource (lib "eagle-import") (part "SS12SDP2"))
    )
    (comp (ref "SMA")
      (value "2985-6004")
      (footprint "eagle-import:29856004")
      (fields (field (name "MOUSER_PART_NUMBER") "523-2985-6004"))
      (libsource (lib "eagle-import") (part "2985-6004"))
    )
    (comp (ref "SPI_1")
      (value "SPI1")
      (footprint "eagle-import:FE10")
      (libsource (lib "eagle-import") (part "FE10-1"))
    )
    (comp (ref "SPI_2")
      (value "SPI0")
      (footprint "eagle-import:FE10")
      (libsource (lib "eagle-import") (part "FE10-1"))
    )
    (comp (ref "SWITCH")
      (value "PINHD-2X4")
      (footprint "eagle-import:2X04")
      (libsource (lib "eagle-import") (part "PINHD-2X4"))
    )
    (comp (ref "U$1")
      (value "2X41_HEADER")
      (footprint "eagle-import:2X41_HEADER")
      (libsource (lib "eagle-import") (part "2X41_HEADER"))
    )
    (comp (ref "U$2")
      (value "2X41_HEADER")
      (footprint "eagle-import:2X41_HEADER")
      (libsource (lib "eagle-import") (part "2X41_HEADER"))
    )
    (comp (ref "U$3")
      (value "2X41_HEADER")
      (footprint "eagle-import:2X41_HEADER")
      (libsource (lib "eagle-import") (part "2X41_HEADER"))
    )
    (comp (ref "U$4")
      (value "2X41_HEADER")
      (footprint "eagle-import:2X41_HEADER")
      (libsource (lib "eagle-import") (part "2X41_HEADER"))
    )
    (comp (ref "U$5")
      (value "RFM95W-915S2")
      (footprint "eagle-import:RFM95W-915S2")
      (libsource (lib "eagle-import") (part "RFM95W-915S2"))
    )
    (comp (ref "USB-UART_1")
      (value "PINHD-1X4")
      (footprint "eagle-import:1X04")
      (libsource (lib "eagle-import") (part "PINHD-1X4"))
    )
    (comp (ref "USB-UART_2")
      (value "PINHD-1X4")
      (footprint "eagle-import:1X04")
      (libsource (lib "eagle-import") (part "PINHD-1X4"))
    )
    (comp (ref "VBN")
      (value "PINHD-1X2")
      (footprint "eagle-import:1X02")
      (libsource (lib "eagle-import") (part "PINHD-1X2"))
    )
    (comp (ref "VBP")
      (value "PINHD-1X2")
      (footprint "eagle-import:1X02")
      (libsource (lib "eagle-import") (part "PINHD-1X2"))
    )
    (comp (ref "VCCQ")
      (value "PINHD-1X2")
      (footprint "eagle-import:1X02")
      (libsource (lib "eagle-import") (part "pinhead_325_PINHD-1X2"))
    )
    (comp (ref "VDD")
      (value "PINHD-1X2")
      (footprint "eagle-import:1X02")
      (libsource (lib "eagle-import") (part "pinhead_325_PINHD-1X2"))
    )
    (comp (ref "VDDH")
      (value "PINHD-1X2")
      (footprint "eagle-import:1X02")
      (libsource (lib "eagle-import") (part "pinhead_325_PINHD-1X2"))
    )
    (comp (ref "VDDLS")
      (value "PINHD-1X2")
      (footprint "eagle-import:1X02")
      (libsource (lib "eagle-import") (part "pinhead_325_PINHD-1X2"))
    )
    (comp (ref "VDD_3V3")
      (value "PINHD-1X2")
      (footprint "eagle-import:1X02")
      (libsource (lib "eagle-import") (part "pinhead_325_PINHD-1X2"))
    )
    (comp (ref "VDD_CORE")
      (value "PINHD-1X2")
      (footprint "eagle-import:1X02")
      (libsource (lib "eagle-import") (part "pinhead_325_PINHD-1X2"))
    )
    (comp (ref "Y1")
      (value "Q13FC1350000400")
      (footprint "eagle-import:Q13FC1350000400")
      (libsource (lib "eagle-import") (part "Q13FC1350000400"))
    )
    (comp (ref "Y3")
      (value "HC-49SM8MHZ20PF30PPM")
      (footprint "eagle-import:HC49SM8MHZ20PF30PPM")
      (fields (field (name "MANUFACTURER_PART_NUMBER") "HC-49SM8MHz20pF30ppm"))
      (libsource (lib "eagle-import") (part "HC-49SM8MHZ20PF30PPM"))
    )
  )
  (nets
    (net (code "1") (name "2") (class "Default")
      (node (ref "U$1") (pin "4") (pinfunction "4_4") (pintype "bidirectional"))
    )
    (net (code "2") (name "4") (class "Default")
      (node (ref "U$1") (pin "6") (pinfunction "6_6") (pintype "bidirectional"))
    )
    (net (code "3") (name "8MHZ_CLOCK") (class "Default")
      (node (ref "CLOCK") (pin "3") (pinfunction "3_3") (pintype "passive"))
      (node (ref "IC12") (pin "4") (pinfunction "Y_4") (pintype "bidirectional"))
      (node (ref "R41") (pin "2") (pinfunction "2_2") (pintype "passive"))
      (node (ref "R44") (pin "1") (pinfunction "1_1") (pintype "passive"))
    )
    (net (code "4") (name "12") (class "Default")
      (node (ref "U$1") (pin "14") (pinfunction "14_14") (pintype "bidirectional"))
    )
    (net (code "5") (name "14") (class "Default")
      (node (ref "U$1") (pin "16") (pinfunction "16_16") (pintype "bidirectional"))
    )
    (net (code "6") (name "16") (class "Default")
      (node (ref "U$1") (pin "18") (pinfunction "18_18") (pintype "bidirectional"))
    )
    (net (code "7") (name "26") (class "Default")
      (node (ref "U$1") (pin "28") (pinfunction "28_28") (pintype "bidirectional"))
    )
    (net (code "8") (name "28") (class "Default")
      (node (ref "U$1") (pin "30") (pinfunction "30_30") (pintype "bidirectional"))
    )
    (net (code "9") (name "32KHZ_CLOCK") (class "Default")
      (node (ref "CLOCK") (pin "1") (pinfunction "1_1") (pintype "passive"))
      (node (ref "IC13") (pin "4") (pinfunction "Y_4") (pintype "bidirectional"))
      (node (ref "R45") (pin "2") (pinfunction "2_2") (pintype "passive"))
      (node (ref "R48") (pin "1") (pinfunction "1_1") (pintype "passive"))
    )
    (net (code "10") (name "36") (class "Default")
      (node (ref "U$1") (pin "38") (pinfunction "38_38") (pintype "bidirectional"))
    )
    (net (code "11") (name "38") (class "Default")
      (node (ref "U$1") (pin "40") (pinfunction "40_40") (pintype "bidirectional"))
    )
    (net (code "12") (name "40") (class "Default")
      (node (ref "U$1") (pin "42") (pinfunction "42_42") (pintype "bidirectional"))
    )
    (net (code "13") (name "41") (class "Default")
      (node (ref "U$2") (pin "1") (pinfunction "1_1") (pintype "bidirectional"))
    )
    (net (code "14") (name "42") (class "Default")
      (node (ref "U$2") (pin "4") (pinfunction "4_4") (pintype "bidirectional"))
    )
    (net (code "15") (name "43") (class "Default")
      (node (ref "U$2") (pin "3") (pinfunction "3_3") (pintype "bidirectional"))
    )
    (net (code "16") (name "44") (class "Default")
      (node (ref "U$2") (pin "6") (pinfunction "6_6") (pintype "bidirectional"))
    )
    (net (code "17") (name "45") (class "Default")
      (node (ref "U$2") (pin "5") (pinfunction "5_5") (pintype "bidirectional"))
    )
    (net (code "18") (name "46") (class "Default")
      (node (ref "U$2") (pin "8") (pinfunction "8_8") (pintype "bidirectional"))
    )
    (net (code "19") (name "47") (class "Default")
      (node (ref "U$2") (pin "7") (pinfunction "7_7") (pintype "bidirectional"))
    )
    (net (code "20") (name "52") (class "Default")
      (node (ref "U$2") (pin "14") (pinfunction "14_14") (pintype "bidirectional"))
    )
    (net (code "21") (name "54") (class "Default")
      (node (ref "U$2") (pin "16") (pinfunction "16_16") (pintype "bidirectional"))
    )
    (net (code "22") (name "56") (class "Default")
      (node (ref "U$2") (pin "18") (pinfunction "18_18") (pintype "bidirectional"))
    )
    (net (code "23") (name "66") (class "Default")
      (node (ref "U$2") (pin "28") (pinfunction "28_28") (pintype "bidirectional"))
    )
    (net (code "24") (name "68") (class "Default")
      (node (ref "U$2") (pin "30") (pinfunction "30_30") (pintype "bidirectional"))
    )
    (net (code "25") (name "73") (class "Default")
      (node (ref "U$2") (pin "33") (pinfunction "33_33") (pintype "bidirectional"))
    )
    (net (code "26") (name "74") (class "Default")
      (node (ref "U$2") (pin "36") (pinfunction "36_36") (pintype "bidirectional"))
    )
    (net (code "27") (name "75") (class "Default")
      (node (ref "U$2") (pin "35") (pinfunction "35_35") (pintype "bidirectional"))
    )
    (net (code "28") (name "76") (class "Default")
      (node (ref "U$2") (pin "38") (pinfunction "38_38") (pintype "bidirectional"))
    )
    (net (code "29") (name "77") (class "Default")
      (node (ref "U$2") (pin "37") (pinfunction "37_37") (pintype "bidirectional"))
    )
    (net (code "30") (name "78") (class "Default")
      (node (ref "U$2") (pin "40") (pinfunction "40_40") (pintype "bidirectional"))
    )
    (net (code "31") (name "79") (class "Default")
      (node (ref "U$2") (pin "39") (pinfunction "39_39") (pintype "bidirectional"))
    )
    (net (code "32") (name "80") (class "Default")
      (node (ref "U$2") (pin "42") (pinfunction "42_42") (pintype "bidirectional"))
    )
    (net (code "33") (name "82") (class "Default")
      (node (ref "U$3") (pin "4") (pinfunction "4_4") (pintype "bidirectional"))
    )
    (net (code "34") (name "83") (class "Default")
      (node (ref "U$3") (pin "3") (pinfunction "3_3") (pintype "bidirectional"))
    )
    (net (code "35") (name "84") (class "Default")
      (node (ref "U$3") (pin "6") (pinfunction "6_6") (pintype "bidirectional"))
    )
    (net (code "36") (name "86") (class "Default")
      (node (ref "U$3") (pin "8") (pinfunction "8_8") (pintype "bidirectional"))
    )
    (net (code "37") (name "88") (class "Default")
      (node (ref "U$3") (pin "10") (pinfunction "10_10") (pintype "bidirectional"))
    )
    (net (code "38") (name "89") (class "Default")
      (node (ref "U$3") (pin "9") (pinfunction "9_9") (pintype "bidirectional"))
    )
    (net (code "39") (name "90") (class "Default")
      (node (ref "U$3") (pin "12") (pinfunction "12_12") (pintype "bidirectional"))
    )
    (net (code "40") (name "91") (class "Default")
      (node (ref "U$3") (pin "11") (pinfunction "11_11") (pintype "bidirectional"))
    )
    (net (code "41") (name "92") (class "Default")
      (node (ref "U$3") (pin "14") (pinfunction "14_14") (pintype "bidirectional"))
    )
    (net (code "42") (name "93") (class "Default")
      (node (ref "U$3") (pin "13") (pinfunction "13_13") (pintype "bidirectional"))
    )
    (net (code "43") (name "94") (class "Default")
      (node (ref "U$3") (pin "16") (pinfunction "16_16") (pintype "bidirectional"))
    )
    (net (code "44") (name "95") (class "Default")
      (node (ref "U$3") (pin "15") (pinfunction "15_15") (pintype "bidirectional"))
    )
    (net (code "45") (name "96") (class "Default")
      (node (ref "U$3") (pin "18") (pinfunction "18_18") (pintype "bidirectional"))
    )
    (net (code "46") (name "97") (class "Default")
      (node (ref "U$3") (pin "17") (pinfunction "17_17") (pintype "bidirectional"))
    )
    (net (code "47") (name "98") (class "Default")
      (node (ref "U$3") (pin "20") (pinfunction "20_20") (pintype "bidirectional"))
    )
    (net (code "48") (name "99") (class "Default")
      (node (ref "U$3") (pin "19") (pinfunction "19_19") (pintype "bidirectional"))
    )
    (net (code "49") (name "101") (class "Default")
      (node (ref "U$3") (pin "21") (pinfunction "21_21") (pintype "bidirectional"))
    )
    (net (code "50") (name "102") (class "Default")
      (node (ref "U$3") (pin "24") (pinfunction "24_24") (pintype "bidirectional"))
    )
    (net (code "51") (name "103") (class "Default")
      (node (ref "U$3") (pin "23") (pinfunction "23_23") (pintype "bidirectional"))
    )
    (net (code "52") (name "104") (class "Default")
      (node (ref "U$3") (pin "26") (pinfunction "26_26") (pintype "bidirectional"))
    )
    (net (code "53") (name "105") (class "Default")
      (node (ref "U$3") (pin "25") (pinfunction "25_25") (pintype "bidirectional"))
    )
    (net (code "54") (name "106") (class "Default")
      (node (ref "U$3") (pin "28") (pinfunction "28_28") (pintype "bidirectional"))
    )
    (net (code "55") (name "107") (class "Default")
      (node (ref "U$3") (pin "27") (pinfunction "27_27") (pintype "bidirectional"))
    )
    (net (code "56") (name "108") (class "Default")
      (node (ref "U$3") (pin "30") (pinfunction "30_30") (pintype "bidirectional"))
    )
    (net (code "57") (name "109") (class "Default")
      (node (ref "U$3") (pin "29") (pinfunction "29_29") (pintype "bidirectional"))
    )
    (net (code "58") (name "110") (class "Default")
      (node (ref "U$3") (pin "32") (pinfunction "32_32") (pintype "bidirectional"))
    )
    (net (code "59") (name "111") (class "Default")
      (node (ref "U$3") (pin "31") (pinfunction "31_31") (pintype "bidirectional"))
    )
    (net (code "60") (name "112") (class "Default")
      (node (ref "U$3") (pin "34") (pinfunction "34_34") (pintype "bidirectional"))
    )
    (net (code "61") (name "113") (class "Default")
      (node (ref "U$3") (pin "33") (pinfunction "33_33") (pintype "bidirectional"))
    )
    (net (code "62") (name "114") (class "Default")
      (node (ref "U$3") (pin "36") (pinfunction "36_36") (pintype "bidirectional"))
    )
    (net (code "63") (name "115") (class "Default")
      (node (ref "U$3") (pin "35") (pinfunction "35_35") (pintype "bidirectional"))
    )
    (net (code "64") (name "116") (class "Default")
      (node (ref "U$3") (pin "38") (pinfunction "38_38") (pintype "bidirectional"))
    )
    (net (code "65") (name "117") (class "Default")
      (node (ref "U$3") (pin "37") (pinfunction "37_37") (pintype "bidirectional"))
    )
    (net (code "66") (name "118") (class "Default")
      (node (ref "U$3") (pin "40") (pinfunction "40_40") (pintype "bidirectional"))
    )
    (net (code "67") (name "119") (class "Default")
      (node (ref "U$3") (pin "39") (pinfunction "39_39") (pintype "bidirectional"))
    )
    (net (code "68") (name "120") (class "Default")
      (node (ref "U$3") (pin "42") (pinfunction "42_42") (pintype "bidirectional"))
    )
    (net (code "69") (name "121") (class "Default")
      (node (ref "U$4") (pin "1") (pinfunction "1_1") (pintype "bidirectional"))
    )
    (net (code "70") (name "122") (class "Default")
      (node (ref "U$4") (pin "4") (pinfunction "4_4") (pintype "bidirectional"))
    )
    (net (code "71") (name "123") (class "Default")
      (node (ref "U$4") (pin "3") (pinfunction "3_3") (pintype "bidirectional"))
    )
    (net (code "72") (name "124") (class "Default")
      (node (ref "U$4") (pin "6") (pinfunction "6_6") (pintype "bidirectional"))
    )
    (net (code "73") (name "125") (class "Default")
      (node (ref "U$4") (pin "5") (pinfunction "5_5") (pintype "bidirectional"))
    )
    (net (code "74") (name "126") (class "Default")
      (node (ref "U$4") (pin "8") (pinfunction "8_8") (pintype "bidirectional"))
    )
    (net (code "75") (name "127") (class "Default")
      (node (ref "U$4") (pin "7") (pinfunction "7_7") (pintype "bidirectional"))
    )
    (net (code "76") (name "128") (class "Default")
      (node (ref "U$4") (pin "10") (pinfunction "10_10") (pintype "bidirectional"))
    )
    (net (code "77") (name "129") (class "Default")
      (node (ref "U$4") (pin "9") (pinfunction "9_9") (pintype "bidirectional"))
    )
    (net (code "78") (name "130") (class "Default")
      (node (ref "U$4") (pin "12") (pinfunction "12_12") (pintype "bidirectional"))
    )
    (net (code "79") (name "131") (class "Default")
      (node (ref "U$4") (pin "11") (pinfunction "11_11") (pintype "bidirectional"))
    )
    (net (code "80") (name "132") (class "Default")
      (node (ref "U$4") (pin "14") (pinfunction "14_14") (pintype "bidirectional"))
    )
    (net (code "81") (name "133") (class "Default")
      (node (ref "U$4") (pin "13") (pinfunction "13_13") (pintype "bidirectional"))
    )
    (net (code "82") (name "134") (class "Default")
      (node (ref "U$4") (pin "16") (pinfunction "16_16") (pintype "bidirectional"))
    )
    (net (code "83") (name "135") (class "Default")
      (node (ref "U$4") (pin "15") (pinfunction "15_15") (pintype "bidirectional"))
    )
    (net (code "84") (name "136") (class "Default")
      (node (ref "U$4") (pin "18") (pinfunction "18_18") (pintype "bidirectional"))
    )
    (net (code "85") (name "137") (class "Default")
      (node (ref "U$4") (pin "17") (pinfunction "17_17") (pintype "bidirectional"))
    )
    (net (code "86") (name "138") (class "Default")
      (node (ref "U$4") (pin "20") (pinfunction "20_20") (pintype "bidirectional"))
    )
    (net (code "87") (name "139") (class "Default")
      (node (ref "U$4") (pin "19") (pinfunction "19_19") (pintype "bidirectional"))
    )
    (net (code "88") (name "140") (class "Default")
      (node (ref "U$4") (pin "22") (pinfunction "22_22") (pintype "bidirectional"))
    )
    (net (code "89") (name "141") (class "Default")
      (node (ref "U$4") (pin "21") (pinfunction "21_21") (pintype "bidirectional"))
    )
    (net (code "90") (name "142") (class "Default")
      (node (ref "U$4") (pin "24") (pinfunction "24_24") (pintype "bidirectional"))
    )
    (net (code "91") (name "143") (class "Default")
      (node (ref "U$4") (pin "23") (pinfunction "23_23") (pintype "bidirectional"))
    )
    (net (code "92") (name "144") (class "Default")
      (node (ref "U$4") (pin "26") (pinfunction "26_26") (pintype "bidirectional"))
    )
    (net (code "93") (name "145") (class "Default")
      (node (ref "U$4") (pin "25") (pinfunction "25_25") (pintype "bidirectional"))
    )
    (net (code "94") (name "146") (class "Default")
      (node (ref "U$4") (pin "28") (pinfunction "28_28") (pintype "bidirectional"))
    )
    (net (code "95") (name "147") (class "Default")
      (node (ref "U$4") (pin "27") (pinfunction "27_27") (pintype "bidirectional"))
    )
    (net (code "96") (name "148") (class "Default")
      (node (ref "U$4") (pin "30") (pinfunction "30_30") (pintype "bidirectional"))
    )
    (net (code "97") (name "149") (class "Default")
      (node (ref "U$4") (pin "29") (pinfunction "29_29") (pintype "bidirectional"))
    )
    (net (code "98") (name "150") (class "Default")
      (node (ref "U$4") (pin "32") (pinfunction "32_32") (pintype "bidirectional"))
    )
    (net (code "99") (name "151") (class "Default")
      (node (ref "U$4") (pin "31") (pinfunction "31_31") (pintype "bidirectional"))
    )
    (net (code "100") (name "152") (class "Default")
      (node (ref "U$4") (pin "34") (pinfunction "34_34") (pintype "bidirectional"))
    )
    (net (code "101") (name "153") (class "Default")
      (node (ref "U$4") (pin "33") (pinfunction "33_33") (pintype "bidirectional"))
    )
    (net (code "102") (name "154") (class "Default")
      (node (ref "U$4") (pin "36") (pinfunction "36_36") (pintype "bidirectional"))
    )
    (net (code "103") (name "155") (class "Default")
      (node (ref "U$4") (pin "35") (pinfunction "35_35") (pintype "bidirectional"))
    )
    (net (code "104") (name "156") (class "Default")
      (node (ref "U$4") (pin "38") (pinfunction "38_38") (pintype "bidirectional"))
    )
    (net (code "105") (name "157") (class "Default")
      (node (ref "U$4") (pin "37") (pinfunction "37_37") (pintype "bidirectional"))
    )
    (net (code "106") (name "158") (class "Default")
      (node (ref "U$4") (pin "40") (pinfunction "40_40") (pintype "bidirectional"))
    )
    (net (code "107") (name "159") (class "Default")
      (node (ref "U$4") (pin "39") (pinfunction "39_39") (pintype "bidirectional"))
    )
    (net (code "108") (name "160") (class "Default")
      (node (ref "U$4") (pin "42") (pinfunction "42_42") (pintype "bidirectional"))
    )
    (net (code "109") (name "DR_ALL_DIPSW[0]") (class "Default")
      (node (ref "SWITCH") (pin "7") (pinfunction "7_7") (pintype "passive"))
      (node (ref "U$1") (pin "22") (pinfunction "22_22") (pintype "bidirectional"))
    )
    (net (code "110") (name "DR_ALL_DIPSW[1]") (class "Default")
      (node (ref "SWITCH") (pin "5") (pinfunction "5_5") (pintype "passive"))
      (node (ref "U$1") (pin "24") (pinfunction "24_24") (pintype "bidirectional"))
    )
    (net (code "111") (name "DR_ALL_DIPSW[2]") (class "Default")
      (node (ref "SWITCH") (pin "3") (pinfunction "3_3") (pintype "passive"))
      (node (ref "U$1") (pin "26") (pinfunction "26_26") (pintype "bidirectional"))
    )
    (net (code "112") (name "DR_ALL_DIPSW[3]") (class "Default")
      (node (ref "SWITCH") (pin "1") (pinfunction "1_1") (pintype "passive"))
      (node (ref "U$1") (pin "25") (pinfunction "25_25") (pintype "bidirectional"))
    )
    (net (code "113") (name "DR_ALL_I_PROG_COPI") (class "Default")
      (node (ref "SPI_2") (pin "2") (pinfunction "2_2") (pintype "passive"))
      (node (ref "U$1") (pin "29") (pinfunction "29_29") (pintype "bidirectional"))
    )
    (net (code "114") (name "DR_ALL_I_PROG_CS") (class "Default")
      (node (ref "SPI_2") (pin "4") (pinfunction "4_4") (pintype "passive"))
      (node (ref "U$1") (pin "33") (pinfunction "33_33") (pintype "bidirectional"))
    )
    (net (code "115") (name "DR_ALL_I_PROG_SCK") (class "Default")
      (node (ref "SPI_2") (pin "1") (pinfunction "1_1") (pintype "passive"))
      (node (ref "U$1") (pin "27") (pinfunction "27_27") (pintype "bidirectional"))
    )
    (net (code "116") (name "DR_ALL_I_SPIFLASH_CIPO") (class "Default")
      (node (ref "FLASH") (pin "8") (pinfunction "8_8") (pintype "passive"))
      (node (ref "U$2") (pin "32") (pinfunction "32_32") (pintype "bidirectional"))
    )
    (net (code "117") (name "DR_ALL_I_SPI_CIPO") (class "Default")
      (node (ref "U$2") (pin "21") (pinfunction "21_21") (pintype "bidirectional"))
      (node (ref "U$5") (pin "P$2") (pinfunction "MISO_P$2") (pintype "bidirectional"))
    )
    (net (code "118") (name "DR_ALL_I_TCK") (class "Default")
      (node (ref "ALL_JTAG") (pin "9") (pinfunction "9_9") (pintype "passive"))
      (node (ref "U$1") (pin "35") (pinfunction "35_35") (pintype "bidirectional"))
    )
    (net (code "119") (name "DR_ALL_I_TDI") (class "Default")
      (node (ref "ALL_JTAG") (pin "5") (pinfunction "5_5") (pintype "passive"))
      (node (ref "U$1") (pin "39") (pinfunction "39_39") (pintype "bidirectional"))
    )
    (net (code "120") (name "DR_ALL_I_TMS") (class "Default")
      (node (ref "ALL_JTAG") (pin "7") (pinfunction "7_7") (pintype "passive"))
      (node (ref "U$2") (pin "12") (pinfunction "12_12") (pintype "bidirectional"))
    )
    (net (code "121") (name "DR_ALL_I_TRST") (class "Default")
      (node (ref "ALL_JTAG") (pin "3") (pinfunction "3_3") (pintype "passive"))
      (node (ref "U$2") (pin "13") (pinfunction "13_13") (pintype "bidirectional"))
    )
    (net (code "122") (name "DR_ALL_LEDS[0]") (class "Default")
      (node (ref "LED") (pin "7") (pinfunction "7_7") (pintype "passive"))
      (node (ref "U$1") (pin "9") (pinfunction "9_9") (pintype "bidirectional"))
    )
    (net (code "123") (name "DR_ALL_LEDS[1]") (class "Default")
      (node (ref "LED") (pin "5") (pinfunction "5_5") (pintype "passive"))
      (node (ref "U$1") (pin "11") (pinfunction "11_11") (pintype "bidirectional"))
    )
    (net (code "124") (name "DR_ALL_LEDS[2]") (class "Default")
      (node (ref "LED") (pin "3") (pinfunction "3_3") (pintype "passive"))
      (node (ref "U$1") (pin "15") (pinfunction "15_15") (pintype "bidirectional"))
    )
    (net (code "125") (name "DR_ALL_LEDS[3]") (class "Default")
      (node (ref "LED") (pin "1") (pinfunction "1_1") (pintype "passive"))
      (node (ref "U$1") (pin "20") (pinfunction "20_20") (pintype "bidirectional"))
    )
    (net (code "126") (name "DR_ALL_O_PROG_CIPO") (class "Default")
      (node (ref "SPI_2") (pin "3") (pinfunction "3_3") (pintype "passive"))
      (node (ref "U$1") (pin "31") (pinfunction "31_31") (pintype "bidirectional"))
    )
    (net (code "127") (name "DR_ALL_O_SPIFLASH_COPI") (class "Default")
      (node (ref "FLASH") (pin "10") (pinfunction "10_10") (pintype "passive"))
      (node (ref "U$2") (pin "29") (pinfunction "29_29") (pintype "bidirectional"))
    )
    (net (code "128") (name "DR_ALL_O_SPIFLASH_CS") (class "Default")
      (node (ref "FLASH") (pin "12") (pinfunction "12_12") (pintype "passive"))
      (node (ref "U$2") (pin "31") (pinfunction "31_31") (pintype "bidirectional"))
    )
    (net (code "129") (name "DR_ALL_O_SPIFLASH_SCK") (class "Default")
      (node (ref "FLASH") (pin "6") (pinfunction "6_6") (pintype "passive"))
      (node (ref "U$2") (pin "25") (pinfunction "25_25") (pintype "bidirectional"))
    )
    (net (code "130") (name "DR_ALL_O_SPI_COPI") (class "Default")
      (node (ref "U$2") (pin "19") (pinfunction "19_19") (pintype "bidirectional"))
      (node (ref "U$5") (pin "P$3") (pinfunction "MOSI_P$3") (pintype "bidirectional"))
    )
    (net (code "131") (name "DR_ALL_O_SPI_CS") (class "Default")
      (node (ref "U$2") (pin "23") (pinfunction "23_23") (pintype "bidirectional"))
      (node (ref "U$5") (pin "P$5") (pinfunction "NSS_P$5") (pintype "bidirectional"))
    )
    (net (code "132") (name "DR_ALL_O_SPI_SCK") (class "Default")
      (node (ref "U$2") (pin "17") (pinfunction "17_17") (pintype "bidirectional"))
      (node (ref "U$5") (pin "P$4") (pinfunction "SCK_P$4") (pintype "bidirectional"))
    )
    (net (code "133") (name "DR_ALL_O_TDO") (class "Default")
      (node (ref "ALL_JTAG") (pin "13") (pinfunction "13_13") (pintype "passive"))
      (node (ref "U$2") (pin "10") (pinfunction "10_10") (pintype "bidirectional"))
    )
    (net (code "134") (name "DR_ALL_RESET") (class "Default")
      (node (ref "RESET") (pin "1") (pinfunction "1_1") (pintype "passive"))
      (node (ref "U$1") (pin "7") (pinfunction "7_7") (pintype "bidirectional"))
    )
    (net (code "135") (name "DR_ALL_RX_IN") (class "Default")
      (node (ref "U$3") (pin "1") (pinfunction "1_1") (pintype "bidirectional"))
      (node (ref "USB-UART_1") (pin "2") (pinfunction "2_2") (pintype "passive"))
    )
    (net (code "136") (name "DR_ALL_TX_OUT") (class "Default")
      (node (ref "U$2") (pin "34") (pinfunction "34_34") (pintype "bidirectional"))
      (node (ref "USB-UART_1") (pin "4") (pinfunction "4_4") (pintype "passive"))
    )
    (net (code "137") (name "DR_CLOCK") (class "Default")
      (node (ref "CLOCK") (pin "2") (pinfunction "2_2") (pintype "passive"))
      (node (ref "CLOCK") (pin "4") (pinfunction "4_4") (pintype "passive"))
      (node (ref "CLOCK") (pin "6") (pinfunction "6_6") (pintype "passive"))
      (node (ref "U$1") (pin "1") (pinfunction "1_1") (pintype "bidirectional"))
    )
    (net (code "138") (name "DR_MUX") (class "Default")
      (node (ref "MUX") (pin "1") (pinfunction "1_1") (pintype "passive"))
      (node (ref "R36") (pin "2") (pinfunction "2_2") (pintype "passive"))
      (node (ref "U$1") (pin "5") (pinfunction "5_5") (pintype "bidirectional"))
    )
    (net (code "139") (name "DR_OPEN8_VDD") (class "Default")
      (node (ref "C37") (pin "1") (pinfunction "1_1") (pintype "passive"))
      (node (ref "C38") (pin "1") (pinfunction "1_1") (pintype "passive"))
      (node (ref "POWER") (pin "8") (pinfunction "8_8") (pintype "passive"))
      (node (ref "POWER_LED") (pin "5") (pinfunction "5_5") (pintype "passive"))
      (node (ref "U$1") (pin "21") (pinfunction "21_21") (pintype "bidirectional"))
    )
    (net (code "140") (name "DR_OPEN8_VDD_LED") (class "Default")
      (node (ref "POWER_LED") (pin "6") (pinfunction "6_6") (pintype "passive"))
      (node (ref "Q5") (pin "1") (pinfunction "G_1") (pintype "bidirectional"))
      (node (ref "R28") (pin "1") (pinfunction "1_1") (pintype "passive"))
    )
    (net (code "141") (name "DR_SERV_VDD") (class "Default")
      (node (ref "C26") (pin "1") (pinfunction "1_1") (pintype "passive"))
      (node (ref "C27") (pin "1") (pinfunction "1_1") (pintype "passive"))
      (node (ref "POWER") (pin "4") (pinfunction "4_4") (pintype "passive"))
      (node (ref "POWER_LED") (pin "1") (pinfunction "1_1") (pintype "passive"))
      (node (ref "U$2") (pin "22") (pinfunction "22_22") (pintype "bidirectional"))
    )
    (net (code "142") (name "DR_SERV_VDD_LED") (class "Default")
      (node (ref "POWER_LED") (pin "2") (pinfunction "2_2") (pintype "passive"))
      (node (ref "Q6") (pin "1") (pinfunction "G_1") (pintype "bidirectional"))
      (node (ref "R30") (pin "1") (pinfunction "1_1") (pintype "passive"))
    )
    (net (code "143") (name "DR_VBN") (class "Default")
      (node (ref "C35") (pin "1") (pinfunction "1_1") (pintype "passive"))
      (node (ref "C36") (pin "1") (pinfunction "1_1") (pintype "passive"))
      (node (ref "U$1") (pin "36") (pinfunction "36_36") (pintype "bidirectional"))
      (node (ref "VBN") (pin "1") (pinfunction "1_1") (pintype "passive"))
    )
    (net (code "144") (name "DR_VBP") (class "Default")
      (node (ref "C32") (pin "1") (pinfunction "1_1") (pintype "passive"))
      (node (ref "C34") (pin "1") (pinfunction "1_1") (pintype "passive"))
      (node (ref "U$1") (pin "37") (pinfunction "37_37") (pintype "bidirectional"))
      (node (ref "VBP") (pin "2") (pinfunction "2_2") (pintype "passive"))
    )
    (net (code "145") (name "DR_VDD") (class "Default")
      (node (ref "C28") (pin "1") (pinfunction "1_1") (pintype "passive"))
      (node (ref "C33") (pin "1") (pinfunction "1_1") (pintype "passive"))
      (node (ref "POWER") (pin "6") (pinfunction "6_6") (pintype "passive"))
      (node (ref "POWER_LED") (pin "3") (pinfunction "3_3") (pintype "passive"))
      (node (ref "U$2") (pin "15") (pinfunction "15_15") (pintype "bidirectional"))
      (node (ref "VBP") (pin "1") (pinfunction "1_1") (pintype "passive"))
    )
    (net (code "146") (name "DR_VDD_LED") (class "Default")
      (node (ref "POWER_LED") (pin "4") (pinfunction "4_4") (pintype "passive"))
      (node (ref "Q7") (pin "1") (pinfunction "G_1") (pintype "bidirectional"))
      (node (ref "R32") (pin "1") (pinfunction "1_1") (pintype "passive"))
    )
    (net (code "147") (name "GND") (class "Default")
      (node (ref "ALL_JTAG") (pin "10") (pinfunction "10_10") (pintype "passive"))
      (node (ref "ALL_JTAG") (pin "12") (pinfunction "12_12") (pintype "passive"))
      (node (ref "ALL_JTAG") (pin "14") (pinfunction "14_14") (pintype "passive"))
      (node (ref "ALL_JTAG") (pin "16") (pinfunction "16_16") (pintype "passive"))
      (node (ref "ALL_JTAG") (pin "18") (pinfunction "18_18") (pintype "passive"))
      (node (ref "ALL_JTAG") (pin "20") (pinfunction "20_20") (pintype "passive"))
      (node (ref "ALL_JTAG") (pin "4") (pinfunction "4_4") (pintype "passive"))
      (node (ref "ALL_JTAG") (pin "6") (pinfunction "6_6") (pintype "passive"))
      (node (ref "ALL_JTAG") (pin "8") (pinfunction "8_8") (pintype "passive"))
      (node (ref "C1") (pin "2") (pinfunction "2_2") (pintype "passive"))
      (node (ref "C10") (pin "2") (pinfunction "2_2") (pintype "passive"))
      (node (ref "C11") (pin "2") (pinfunction "2_2") (pintype "passive"))
      (node (ref "C12") (pin "2") (pinfunction "2_2") (pintype "passive"))
      (node (ref "C2") (pin "2") (pinfunction "2_2") (pintype "passive"))
      (node (ref "C22") (pin "2") (pinfunction "2_2") (pintype "passive"))
      (node (ref "C24") (pin "1") (pinfunction "1_1") (pintype "passive"))
      (node (ref "C25") (pin "2") (pinfunction "2_2") (pintype "passive"))
      (node (ref "C26") (pin "2") (pinfunction "2_2") (pintype "passive"))
      (node (ref "C27") (pin "2") (pinfunction "2_2") (pintype "passive"))
      (node (ref "C28") (pin "2") (pinfunction "2_2") (pintype "passive"))
      (node (ref "C29") (pin "1") (pinfunction "1_1") (pintype "passive"))
      (node (ref "C3") (pin "2") (pinfunction "2_2") (pintype "passive"))
      (node (ref "C30") (pin "1") (pinfunction "1_1") (pintype "passive"))
      (node (ref "C31") (pin "1") (pinfunction "1_1") (pintype "passive"))
      (node (ref "C32") (pin "2") (pinfunction "2_2") (pintype "passive"))
      (node (ref "C33") (pin "2") (pinfunction "2_2") (pintype "passive"))
      (node (ref "C34") (pin "2") (pinfunction "2_2") (pintype "passive"))
      (node (ref "C35") (pin "2") (pinfunction "2_2") (pintype "passive"))
      (node (ref "C36") (pin "2") (pinfunction "2_2") (pintype "passive"))
      (node (ref "C37") (pin "2") (pinfunction "2_2") (pintype "passive"))
      (node (ref "C38") (pin "2") (pinfunction "2_2") (pintype "passive"))
      (node (ref "C39") (pin "2") (pinfunction "2_2") (pintype "passive"))
      (node (ref "C4") (pin "2") (pinfunction "2_2") (pintype "passive"))
      (node (ref "C40") (pin "2") (pinfunction "2_2") (pintype "passive"))
      (node (ref "C41") (pin "2") (pinfunction "2_2") (pintype "passive"))
      (node (ref "C42") (pin "2") (pinfunction "2_2") (pintype "passive"))
      (node (ref "C5") (pin "2") (pinfunction "2_2") (pintype "passive"))
      (node (ref "C6") (pin "2") (pinfunction "2_2") (pintype "passive"))
      (node (ref "C7") (pin "2") (pinfunction "2_2") (pintype "passive"))
      (node (ref "C8") (pin "2") (pinfunction "2_2") (pintype "passive"))
      (node (ref "C9") (pin "2") (pinfunction "2_2") (pintype "passive"))
      (node (ref "FLASH") (pin "3") (pinfunction "3_3") (pintype "passive"))
      (node (ref "FLASH") (pin "4") (pinfunction "4_4") (pintype "passive"))
      (node (ref "GND") (pin "1") (pinfunction "1_1") (pintype "passive"))
      (node (ref "GND") (pin "2") (pinfunction "2_2") (pintype "passive"))
      (node (ref "GND") (pin "3") (pinfunction "3_3") (pintype "passive"))
      (node (ref "GND") (pin "4") (pinfunction "4_4") (pintype "passive"))
      (node (ref "GND") (pin "5") (pinfunction "5_5") (pintype "passive"))
      (node (ref "GND") (pin "6") (pinfunction "6_6") (pintype "passive"))
      (node (ref "IC1") (pin "2") (pinfunction "GND_2") (pintype "bidirectional"))
      (node (ref "IC2") (pin "2") (pinfunction "GND_2") (pintype "bidirectional"))
      (node (ref "IC5") (pin "2") (pinfunction "GND_2") (pintype "bidirectional"))
      (node (ref "IC7") (pin "2") (pinfunction "GND_2") (pintype "bidirectional"))
      (node (ref "IC8") (pin "2") (pinfunction "GND_2") (pintype "bidirectional"))
      (node (ref "IC9") (pin "2") (pinfunction "GND_2") (pintype "bidirectional"))
      (node (ref "MUX") (pin "2") (pinfunction "2_2") (pintype "passive"))
      (node (ref "Q1") (pin "2") (pinfunction "S_2") (pintype "bidirectional"))
      (node (ref "Q10") (pin "2") (pinfunction "S_2") (pintype "bidirectional"))
      (node (ref "Q11") (pin "2") (pinfunction "S_2") (pintype "bidirectional"))
      (node (ref "Q12") (pin "2") (pinfunction "S_2") (pintype "bidirectional"))
      (node (ref "Q2") (pin "2") (pinfunction "S_2") (pintype "bidirectional"))
      (node (ref "Q3") (pin "2") (pinfunction "S_2") (pintype "bidirectional"))
      (node (ref "Q4") (pin "2") (pinfunction "S_2") (pintype "bidirectional"))
      (node (ref "Q5") (pin "2") (pinfunction "S_2") (pintype "bidirectional"))
      (node (ref "Q6") (pin "2") (pinfunction "S_2") (pintype "bidirectional"))
      (node (ref "Q7") (pin "2") (pinfunction "S_2") (pintype "bidirectional"))
      (node (ref "Q8") (pin "2") (pinfunction "S_2") (pintype "bidirectional"))
      (node (ref "Q9") (pin "2") (pinfunction "S_2") (pintype "bidirectional"))
      (node (ref "R1") (pin "2") (pinfunction "2_2") (pintype "passive"))
      (node (ref "R10") (pin "2") (pinfunction "2_2") (pintype "passive"))
      (node (ref "R13") (pin "2") (pinfunction "2_2") (pintype "passive"))
      (node (ref "R17") (pin "2") (pinfunction "2_2") (pintype "passive"))
      (node (ref "R19") (pin "2") (pinfunction "2_2") (pintype "passive"))
      (node (ref "R21") (pin "2") (pinfunction "2_2") (pintype "passive"))
      (node (ref "R23") (pin "2") (pinfunction "2_2") (pintype "passive"))
      (node (ref "R24") (pin "2") (pinfunction "2_2") (pintype "passive"))
      (node (ref "R28") (pin "2") (pinfunction "2_2") (pintype "passive"))
      (node (ref "R30") (pin "2") (pinfunction "2_2") (pintype "passive"))
      (node (ref "R32") (pin "2") (pinfunction "2_2") (pintype "passive"))
      (node (ref "R35") (pin "2") (pinfunction "2_2") (pintype "passive"))
      (node (ref "R38") (pin "2") (pinfunction "2_2") (pintype "passive"))
      (node (ref "R4") (pin "2") (pinfunction "2_2") (pintype "passive"))
      (node (ref "R40") (pin "2") (pinfunction "2_2") (pintype "passive"))
      (node (ref "R43") (pin "1") (pinfunction "1_1") (pintype "passive"))
      (node (ref "R47") (pin "1") (pinfunction "1_1") (pintype "passive"))
      (node (ref "R50") (pin "2") (pinfunction "2_2") (pintype "passive"))
      (node (ref "R52") (pin "2") (pinfunction "2_2") (pintype "passive"))
      (node (ref "R7") (pin "2") (pinfunction "2_2") (pintype "passive"))
      (node (ref "S1") (pin "3") (pinfunction "ON_2_3") (pintype "bidirectional"))
      (node (ref "S2") (pin "3") (pinfunction "ON_2_3") (pintype "bidirectional"))
      (node (ref "S3") (pin "3") (pinfunction "ON_2_3") (pintype "bidirectional"))
      (node (ref "S4") (pin "3") (pinfunction "ON_2_3") (pintype "bidirectional"))
      (node (ref "S5") (pin "3") (pinfunction "ON_2_3") (pintype "bidirectional"))
      (node (ref "SMA") (pin "1") (pinfunction "1_1") (pintype "bidirectional"))
      (node (ref "SMA") (pin "2") (pinfunction "2_2") (pintype "bidirectional"))
      (node (ref "SMA") (pin "3") (pinfunction "3_3") (pintype "bidirectional"))
      (node (ref "SMA") (pin "4") (pinfunction "4_4") (pintype "bidirectional"))
      (node (ref "SPI_2") (pin "10") (pinfunction "10_10") (pintype "passive"))
      (node (ref "U$1") (pin "12") (pinfunction "12_12") (pintype "bidirectional"))
      (node (ref "U$1") (pin "19") (pinfunction "19_19") (pintype "bidirectional"))
      (node (ref "U$1") (pin "23") (pinfunction "23_23") (pintype "bidirectional"))
      (node (ref "U$1") (pin "34") (pinfunction "34_34") (pintype "bidirectional"))
      (node (ref "U$1") (pin "8") (pinfunction "8_8") (pintype "bidirectional"))
      (node (ref "U$2") (pin "11") (pinfunction "11_11") (pintype "bidirectional"))
      (node (ref "U$2") (pin "20") (pinfunction "20_20") (pintype "bidirectional"))
      (node (ref "U$2") (pin "24") (pinfunction "24_24") (pintype "bidirectional"))
      (node (ref "U$2") (pin "27") (pinfunction "27_27") (pintype "bidirectional"))
      (node (ref "U$3") (pin "22") (pinfunction "22_22") (pintype "bidirectional"))
      (node (ref "U$3") (pin "7") (pinfunction "7_7") (pintype "bidirectional"))
      (node (ref "U$5") (pin "P$1") (pinfunction "GND_1_P$1") (pintype "bidirectional"))
      (node (ref "U$5") (pin "P$15") (pinfunction "GND_3_P$15") (pintype "bidirectional"))
      (node (ref "U$5") (pin "P$8") (pinfunction "GND_2_P$8") (pintype "bidirectional"))
      (node (ref "USB-UART_1") (pin "1") (pinfunction "1_1") (pintype "passive"))
      (node (ref "VBN") (pin "2") (pinfunction "2_2") (pintype "passive"))
    )
    (net (code "148") (name "IN_VDD") (class "Default")
      (node (ref "C9") (pin "1") (pinfunction "1_1") (pintype "passive"))
      (node (ref "IC9") (pin "1") (pinfunction "IN_1") (pintype "bidirectional"))
      (node (ref "IC9") (pin "3") (pinfunction "EN_3") (pintype "bidirectional"))
      (node (ref "VDD") (pin "2") (pinfunction "2_2") (pintype "passive"))
    )
    (net (code "149") (name "IN_VDDH") (class "Default")
      (node (ref "C1") (pin "1") (pinfunction "1_1") (pintype "passive"))
      (node (ref "IC2") (pin "1") (pinfunction "IN_1") (pintype "bidirectional"))
      (node (ref "IC2") (pin "3") (pinfunction "EN_3") (pintype "bidirectional"))
      (node (ref "VDDH") (pin "2") (pinfunction "2_2") (pintype "passive"))
    )
    (net (code "150") (name "IN_VDDLS") (class "Default")
      (node (ref "C22") (pin "1") (pinfunction "1_1") (pintype "passive"))
      (node (ref "IC1") (pin "1") (pinfunction "IN_1") (pintype "bidirectional"))
      (node (ref "IC1") (pin "3") (pinfunction "EN_3") (pintype "bidirectional"))
      (node (ref "VDDLS") (pin "2") (pinfunction "2_2") (pintype "passive"))
    )
    (net (code "151") (name "IN_VDDQ") (class "Default")
      (node (ref "C3") (pin "1") (pinfunction "1_1") (pintype "passive"))
      (node (ref "IC5") (pin "1") (pinfunction "IN_1") (pintype "bidirectional"))
      (node (ref "IC5") (pin "3") (pinfunction "EN_3") (pintype "bidirectional"))
      (node (ref "VCCQ") (pin "2") (pinfunction "2_2") (pintype "passive"))
    )
    (net (code "152") (name "IN_VDD_3V3") (class "Default")
      (node (ref "C5") (pin "1") (pinfunction "1_1") (pintype "passive"))
      (node (ref "IC7") (pin "1") (pinfunction "IN_1") (pintype "bidirectional"))
      (node (ref "IC7") (pin "3") (pinfunction "EN_3") (pintype "bidirectional"))
      (node (ref "VDD_3V3") (pin "2") (pinfunction "2_2") (pintype "passive"))
    )
    (net (code "153") (name "IN_VDD_CORE") (class "Default")
      (node (ref "C7") (pin "1") (pinfunction "1_1") (pintype "passive"))
      (node (ref "IC8") (pin "1") (pinfunction "IN_1") (pintype "bidirectional"))
      (node (ref "IC8") (pin "3") (pinfunction "EN_3") (pintype "bidirectional"))
      (node (ref "VDD_CORE") (pin "2") (pinfunction "2_2") (pintype "passive"))
    )
    (net (code "154") (name "LED_0") (class "Default")
      (node (ref "LED") (pin "8") (pinfunction "8_8") (pintype "passive"))
      (node (ref "Q9") (pin "1") (pinfunction "G_1") (pintype "bidirectional"))
      (node (ref "R38") (pin "1") (pinfunction "1_1") (pintype "passive"))
    )
    (net (code "155") (name "LED_1") (class "Default")
      (node (ref "LED") (pin "6") (pinfunction "6_6") (pintype "passive"))
      (node (ref "Q10") (pin "1") (pinfunction "G_1") (pintype "bidirectional"))
      (node (ref "R40") (pin "1") (pinfunction "1_1") (pintype "passive"))
    )
    (net (code "156") (name "LED_2") (class "Default")
      (node (ref "LED") (pin "4") (pinfunction "4_4") (pintype "passive"))
      (node (ref "Q11") (pin "1") (pinfunction "G_1") (pintype "bidirectional"))
      (node (ref "R50") (pin "1") (pinfunction "1_1") (pintype "passive"))
    )
    (net (code "157") (name "LED_3") (class "Default")
      (node (ref "LED") (pin "2") (pinfunction "2_2") (pintype "passive"))
      (node (ref "Q12") (pin "1") (pinfunction "G_1") (pintype "bidirectional"))
      (node (ref "R52") (pin "1") (pinfunction "1_1") (pintype "passive"))
    )
    (net (code "158") (name "Net-(IC1-ADJ)") (class "Default")
      (node (ref "IC1") (pin "4") (pinfunction "ADJ_4") (pintype "bidirectional"))
      (node (ref "R24") (pin "1") (pinfunction "1_1") (pintype "passive"))
      (node (ref "R25") (pin "2") (pinfunction "2_2") (pintype "passive"))
    )
    (net (code "159") (name "Net-(IC2-ADJ)") (class "Default")
      (node (ref "IC2") (pin "4") (pinfunction "ADJ_4") (pintype "bidirectional"))
      (node (ref "R1") (pin "1") (pinfunction "1_1") (pintype "passive"))
      (node (ref "R2") (pin "2") (pinfunction "2_2") (pintype "passive"))
    )
    (net (code "160") (name "Net-(IC5-ADJ)") (class "Default")
      (node (ref "IC5") (pin "4") (pinfunction "ADJ_4") (pintype "bidirectional"))
      (node (ref "R4") (pin "1") (pinfunction "1_1") (pintype "passive"))
      (node (ref "R5") (pin "2") (pinfunction "2_2") (pintype "passive"))
    )
    (net (code "161") (name "Net-(IC7-ADJ)") (class "Default")
      (node (ref "IC7") (pin "4") (pinfunction "ADJ_4") (pintype "bidirectional"))
      (node (ref "R7") (pin "1") (pinfunction "1_1") (pintype "passive"))
      (node (ref "R8") (pin "2") (pinfunction "2_2") (pintype "passive"))
    )
    (net (code "162") (name "Net-(IC8-ADJ)") (class "Default")
      (node (ref "IC8") (pin "4") (pinfunction "ADJ_4") (pintype "bidirectional"))
      (node (ref "R10") (pin "1") (pinfunction "1_1") (pintype "passive"))
      (node (ref "R11") (pin "2") (pinfunction "2_2") (pintype "passive"))
    )
    (net (code "163") (name "Net-(IC9-ADJ)") (class "Default")
      (node (ref "IC9") (pin "4") (pinfunction "ADJ_4") (pintype "bidirectional"))
      (node (ref "R13") (pin "1") (pinfunction "1_1") (pintype "passive"))
      (node (ref "R14") (pin "2") (pinfunction "2_2") (pintype "passive"))
    )
    (net (code "164") (name "Net-(IC12-A)") (class "Default")
      (node (ref "C29") (pin "2") (pinfunction "2_2") (pintype "passive"))
      (node (ref "IC12") (pin "2") (pinfunction "A_2") (pintype "bidirectional"))
      (node (ref "R41") (pin "1") (pinfunction "1_1") (pintype "passive"))
      (node (ref "Y3") (pin "2") (pinfunction "CRYSTAL_2_2") (pintype "bidirectional"))
    )
    (net (code "165") (name "Net-(IC12-GND)") (class "Default")
      (node (ref "IC12") (pin "3") (pinfunction "GND_3") (pintype "power_in"))
      (node (ref "R43") (pin "2") (pinfunction "2_2") (pintype "passive"))
    )
    (net (code "166") (name "Net-(IC12-VCC)") (class "Default")
      (node (ref "IC12") (pin "5") (pinfunction "VCC_5") (pintype "power_in"))
      (node (ref "R42") (pin "1") (pinfunction "1_1") (pintype "passive"))
    )
    (net (code "167") (name "Net-(IC13-A)") (class "Default")
      (node (ref "C31") (pin "2") (pinfunction "2_2") (pintype "passive"))
      (node (ref "IC13") (pin "2") (pinfunction "A_2") (pintype "bidirectional"))
      (node (ref "R45") (pin "1") (pinfunction "1_1") (pintype "passive"))
      (node (ref "Y1") (pin "2") (pinfunction "CRYSTAL_2_2") (pintype "bidirectional"))
    )
    (net (code "168") (name "Net-(IC13-GND)") (class "Default")
      (node (ref "IC13") (pin "3") (pinfunction "GND_3") (pintype "power_in"))
      (node (ref "R47") (pin "2") (pinfunction "2_2") (pintype "passive"))
    )
    (net (code "169") (name "Net-(IC13-VCC)") (class "Default")
      (node (ref "IC13") (pin "5") (pinfunction "VCC_5") (pintype "power_in"))
      (node (ref "R46") (pin "1") (pinfunction "1_1") (pintype "passive"))
    )
    (net (code "170") (name "Net-(LED1-PadA)") (class "Default")
      (node (ref "LED1") (pin "A") (pinfunction "A_A") (pintype "passive"))
      (node (ref "R16") (pin "1") (pinfunction "1_1") (pintype "passive"))
    )
    (net (code "171") (name "Net-(LED2-PadA)") (class "Default")
      (node (ref "LED2") (pin "A") (pinfunction "A_A") (pintype "passive"))
      (node (ref "R18") (pin "1") (pinfunction "1_1") (pintype "passive"))
    )
    (net (code "172") (name "Net-(LED3-PadA)") (class "Default")
      (node (ref "LED3") (pin "A") (pinfunction "A_A") (pintype "passive"))
      (node (ref "R20") (pin "1") (pinfunction "1_1") (pintype "passive"))
    )
    (net (code "173") (name "Net-(LED4-PadA)") (class "Default")
      (node (ref "LED4") (pin "A") (pinfunction "A_A") (pintype "passive"))
      (node (ref "R22") (pin "1") (pinfunction "1_1") (pintype "passive"))
    )
    (net (code "174") (name "Net-(LED5-PadA)") (class "Default")
      (node (ref "LED5") (pin "A") (pinfunction "A_A") (pintype "passive"))
      (node (ref "R27") (pin "1") (pinfunction "1_1") (pintype "passive"))
    )
    (net (code "175") (name "Net-(LED6-PadA)") (class "Default")
      (node (ref "LED6") (pin "A") (pinfunction "A_A") (pintype "passive"))
      (node (ref "R29") (pin "1") (pinfunction "1_1") (pintype "passive"))
    )
    (net (code "176") (name "Net-(LED7-PadA)") (class "Default")
      (node (ref "LED7") (pin "A") (pinfunction "A_A") (pintype "passive"))
      (node (ref "R31") (pin "1") (pinfunction "1_1") (pintype "passive"))
    )
    (net (code "177") (name "Net-(LED8-PadA)") (class "Default")
      (node (ref "LED8") (pin "A") (pinfunction "A_A") (pintype "passive"))
      (node (ref "R33") (pin "1") (pinfunction "1_1") (pintype "passive"))
    )
    (net (code "178") (name "Net-(LED9-PadA)") (class "Default")
      (node (ref "LED9") (pin "A") (pinfunction "A_A") (pintype "passive"))
      (node (ref "R37") (pin "1") (pinfunction "1_1") (pintype "passive"))
    )
    (net (code "179") (name "Net-(LED10-PadA)") (class "Default")
      (node (ref "LED10") (pin "A") (pinfunction "A_A") (pintype "passive"))
      (node (ref "R39") (pin "1") (pinfunction "1_1") (pintype "passive"))
    )
    (net (code "180") (name "Net-(LED11-PadA)") (class "Default")
      (node (ref "LED11") (pin "A") (pinfunction "A_A") (pintype "passive"))
      (node (ref "R49") (pin "1") (pinfunction "1_1") (pintype "passive"))
    )
    (net (code "181") (name "Net-(LED12-PadA)") (class "Default")
      (node (ref "LED12") (pin "A") (pinfunction "A_A") (pintype "passive"))
      (node (ref "R51") (pin "1") (pinfunction "1_1") (pintype "passive"))
    )
    (net (code "182") (name "Net-(Q1-D)") (class "Default")
      (node (ref "LED2") (pin "C") (pinfunction "C_C") (pintype "passive"))
      (node (ref "Q1") (pin "3") (pinfunction "D_3") (pintype "bidirectional"))
    )
    (net (code "183") (name "Net-(Q2-D)") (class "Default")
      (node (ref "LED3") (pin "C") (pinfunction "C_C") (pintype "passive"))
      (node (ref "Q2") (pin "3") (pinfunction "D_3") (pintype "bidirectional"))
    )
    (net (code "184") (name "Net-(Q3-D)") (class "Default")
      (node (ref "LED1") (pin "C") (pinfunction "C_C") (pintype "passive"))
      (node (ref "Q3") (pin "3") (pinfunction "D_3") (pintype "bidirectional"))
    )
    (net (code "185") (name "Net-(Q4-D)") (class "Default")
      (node (ref "LED4") (pin "C") (pinfunction "C_C") (pintype "passive"))
      (node (ref "Q4") (pin "3") (pinfunction "D_3") (pintype "bidirectional"))
    )
    (net (code "186") (name "Net-(Q5-D)") (class "Default")
      (node (ref "LED5") (pin "C") (pinfunction "C_C") (pintype "passive"))
      (node (ref "Q5") (pin "3") (pinfunction "D_3") (pintype "bidirectional"))
    )
    (net (code "187") (name "Net-(Q6-D)") (class "Default")
      (node (ref "LED6") (pin "C") (pinfunction "C_C") (pintype "passive"))
      (node (ref "Q6") (pin "3") (pinfunction "D_3") (pintype "bidirectional"))
    )
    (net (code "188") (name "Net-(Q7-D)") (class "Default")
      (node (ref "LED7") (pin "C") (pinfunction "C_C") (pintype "passive"))
      (node (ref "Q7") (pin "3") (pinfunction "D_3") (pintype "bidirectional"))
    )
    (net (code "189") (name "Net-(Q8-D)") (class "Default")
      (node (ref "LED8") (pin "C") (pinfunction "C_C") (pintype "passive"))
      (node (ref "Q8") (pin "3") (pinfunction "D_3") (pintype "bidirectional"))
    )
    (net (code "190") (name "Net-(Q9-D)") (class "Default")
      (node (ref "LED9") (pin "C") (pinfunction "C_C") (pintype "passive"))
      (node (ref "Q9") (pin "3") (pinfunction "D_3") (pintype "bidirectional"))
    )
    (net (code "191") (name "Net-(Q10-D)") (class "Default")
      (node (ref "LED10") (pin "C") (pinfunction "C_C") (pintype "passive"))
      (node (ref "Q10") (pin "3") (pinfunction "D_3") (pintype "bidirectional"))
    )
    (net (code "192") (name "Net-(Q11-D)") (class "Default")
      (node (ref "LED11") (pin "C") (pinfunction "C_C") (pintype "passive"))
      (node (ref "Q11") (pin "3") (pinfunction "D_3") (pintype "bidirectional"))
    )
    (net (code "193") (name "Net-(Q12-D)") (class "Default")
      (node (ref "LED12") (pin "C") (pinfunction "C_C") (pintype "passive"))
      (node (ref "Q12") (pin "3") (pinfunction "D_3") (pintype "bidirectional"))
    )
    (net (code "194") (name "Net-(S1-COM)") (class "Default")
      (node (ref "RESET") (pin "2") (pinfunction "2_2") (pintype "passive"))
      (node (ref "S1") (pin "2") (pinfunction "COM_2") (pintype "bidirectional"))
    )
    (net (code "195") (name "Net-(S1-ON_1)") (class "Default")
      (node (ref "R34") (pin "1") (pinfunction "1_1") (pintype "passive"))
      (node (ref "S1") (pin "1") (pinfunction "ON_1_1") (pintype "bidirectional"))
    )
    (net (code "196") (name "Net-(S2-COM)") (class "Default")
      (node (ref "S2") (pin "2") (pinfunction "COM_2") (pintype "bidirectional"))
      (node (ref "SWITCH") (pin "2") (pinfunction "2_2") (pintype "passive"))
    )
    (net (code "197") (name "Net-(S2-ON_1)") (class "Default")
      (node (ref "R53") (pin "1") (pinfunction "1_1") (pintype "passive"))
      (node (ref "S2") (pin "1") (pinfunction "ON_1_1") (pintype "bidirectional"))
    )
    (net (code "198") (name "Net-(S3-COM)") (class "Default")
      (node (ref "S3") (pin "2") (pinfunction "COM_2") (pintype "bidirectional"))
      (node (ref "SWITCH") (pin "4") (pinfunction "4_4") (pintype "passive"))
    )
    (net (code "199") (name "Net-(S3-ON_1)") (class "Default")
      (node (ref "R54") (pin "1") (pinfunction "1_1") (pintype "passive"))
      (node (ref "S3") (pin "1") (pinfunction "ON_1_1") (pintype "bidirectional"))
    )
    (net (code "200") (name "Net-(S4-COM)") (class "Default")
      (node (ref "S4") (pin "2") (pinfunction "COM_2") (pintype "bidirectional"))
      (node (ref "SWITCH") (pin "6") (pinfunction "6_6") (pintype "passive"))
    )
    (net (code "201") (name "Net-(S4-ON_1)") (class "Default")
      (node (ref "R55") (pin "1") (pinfunction "1_1") (pintype "passive"))
      (node (ref "S4") (pin "1") (pinfunction "ON_1_1") (pintype "bidirectional"))
    )
    (net (code "202") (name "Net-(S5-COM)") (class "Default")
      (node (ref "S5") (pin "2") (pinfunction "COM_2") (pintype "bidirectional"))
      (node (ref "SWITCH") (pin "8") (pinfunction "8_8") (pintype "passive"))
    )
    (net (code "203") (name "Net-(S5-ON_1)") (class "Default")
      (node (ref "R56") (pin "1") (pinfunction "1_1") (pintype "passive"))
      (node (ref "S5") (pin "1") (pinfunction "ON_1_1") (pintype "bidirectional"))
    )
    (net (code "204") (name "Net-(Y1-CRYSTAL_1)") (class "Default")
      (node (ref "C30") (pin "2") (pinfunction "2_2") (pintype "passive"))
      (node (ref "R48") (pin "2") (pinfunction "2_2") (pintype "passive"))
      (node (ref "Y1") (pin "1") (pinfunction "CRYSTAL_1_1") (pintype "bidirectional"))
    )
    (net (code "205") (name "Net-(Y3-CRYSTAL_1)") (class "Default")
      (node (ref "C24") (pin "2") (pinfunction "2_2") (pintype "passive"))
      (node (ref "R44") (pin "2") (pinfunction "2_2") (pintype "passive"))
      (node (ref "Y3") (pin "1") (pinfunction "CRYSTAL_1_1") (pintype "bidirectional"))
    )
    (net (code "206") (name "OUT_VDD") (class "Default")
      (node (ref "C10") (pin "1") (pinfunction "1_1") (pintype "passive"))
      (node (ref "IC9") (pin "5") (pinfunction "OUT_5") (pintype "bidirectional"))
      (node (ref "POWER") (pin "5") (pinfunction "5_5") (pintype "passive"))
      (node (ref "R14") (pin "1") (pinfunction "1_1") (pintype "passive"))
    )
    (net (code "207") (name "OUT_VDDH") (class "Default")
      (node (ref "C2") (pin "1") (pinfunction "1_1") (pintype "passive"))
      (node (ref "IC2") (pin "5") (pinfunction "OUT_5") (pintype "bidirectional"))
      (node (ref "POWER") (pin "11") (pinfunction "11_11") (pintype "passive"))
      (node (ref "R2") (pin "1") (pinfunction "1_1") (pintype "passive"))
    )
    (net (code "208") (name "OUT_VDDLS") (class "Default")
      (node (ref "C25") (pin "1") (pinfunction "1_1") (pintype "passive"))
      (node (ref "IC1") (pin "5") (pinfunction "OUT_5") (pintype "bidirectional"))
      (node (ref "POWER") (pin "9") (pinfunction "9_9") (pintype "passive"))
      (node (ref "R25") (pin "1") (pinfunction "1_1") (pintype "passive"))
    )
    (net (code "209") (name "OUT_VDDQ") (class "Default")
      (node (ref "C4") (pin "1") (pinfunction "1_1") (pintype "passive"))
      (node (ref "IC5") (pin "5") (pinfunction "OUT_5") (pintype "bidirectional"))
      (node (ref "POWER") (pin "1") (pinfunction "1_1") (pintype "passive"))
      (node (ref "R5") (pin "1") (pinfunction "1_1") (pintype "passive"))
    )
    (net (code "210") (name "OUT_VDD_3V3") (class "Default")
      (node (ref "C6") (pin "1") (pinfunction "1_1") (pintype "passive"))
      (node (ref "IC7") (pin "5") (pinfunction "OUT_5") (pintype "bidirectional"))
      (node (ref "POWER") (pin "13") (pinfunction "13_13") (pintype "passive"))
      (node (ref "R8") (pin "1") (pinfunction "1_1") (pintype "passive"))
    )
    (net (code "211") (name "OUT_VDD_CORE") (class "Default")
      (node (ref "C8") (pin "1") (pinfunction "1_1") (pintype "passive"))
      (node (ref "IC8") (pin "5") (pinfunction "OUT_5") (pintype "bidirectional"))
      (node (ref "POWER") (pin "3") (pinfunction "3_3") (pintype "passive"))
      (node (ref "POWER") (pin "7") (pinfunction "7_7") (pintype "passive"))
      (node (ref "R11") (pin "1") (pinfunction "1_1") (pintype "passive"))
    )
    (net (code "212") (name "SMA_CLK") (class "Default")
      (node (ref "CLOCK") (pin "5") (pinfunction "5_5") (pintype "passive"))
      (node (ref "SMA") (pin "5") (pinfunction "5_5") (pintype "bidirectional"))
    )
    (net (code "213") (name "VCCQ") (class "Default")
      (node (ref "C11") (pin "1") (pinfunction "1_1") (pintype "passive"))
      (node (ref "C12") (pin "1") (pinfunction "1_1") (pintype "passive"))
      (node (ref "POWER") (pin "2") (pinfunction "2_2") (pintype "passive"))
      (node (ref "Q2") (pin "1") (pinfunction "G_1") (pintype "bidirectional"))
      (node (ref "R21") (pin "1") (pinfunction "1_1") (pintype "passive"))
      (node (ref "U$1") (pin "17") (pinfunction "17_17") (pintype "bidirectional"))
      (node (ref "U$1") (pin "3") (pinfunction "3_3") (pintype "bidirectional"))
      (node (ref "U$1") (pin "32") (pinfunction "32_32") (pintype "bidirectional"))
      (node (ref "U$2") (pin "26") (pinfunction "26_26") (pintype "bidirectional"))
      (node (ref "U$2") (pin "9") (pinfunction "9_9") (pintype "bidirectional"))
      (node (ref "U$3") (pin "5") (pinfunction "5_5") (pintype "bidirectional"))
    )
    (net (code "214") (name "VDDH") (class "Default")
      (node (ref "C41") (pin "1") (pinfunction "1_1") (pintype "passive"))
      (node (ref "C42") (pin "1") (pinfunction "1_1") (pintype "passive"))
      (node (ref "POWER") (pin "12") (pinfunction "12_12") (pintype "passive"))
      (node (ref "Q1") (pin "1") (pinfunction "G_1") (pintype "bidirectional"))
      (node (ref "R19") (pin "1") (pinfunction "1_1") (pintype "passive"))
      (node (ref "U$1") (pin "10") (pinfunction "10_10") (pintype "bidirectional"))
    )
    (net (code "215") (name "VDDLS") (class "Default")
      (node (ref "C39") (pin "1") (pinfunction "1_1") (pintype "passive"))
      (node (ref "C40") (pin "1") (pinfunction "1_1") (pintype "passive"))
      (node (ref "POWER") (pin "10") (pinfunction "10_10") (pintype "passive"))
      (node (ref "Q3") (pin "1") (pinfunction "G_1") (pintype "bidirectional"))
      (node (ref "R17") (pin "1") (pinfunction "1_1") (pintype "passive"))
      (node (ref "U$1") (pin "13") (pinfunction "13_13") (pintype "bidirectional"))
    )
    (net (code "216") (name "VDD_3V3") (class "Default")
      (node (ref "ALL_JTAG") (pin "1") (pinfunction "1_1") (pintype "passive"))
      (node (ref "ALL_JTAG") (pin "2") (pinfunction "2_2") (pintype "passive"))
      (node (ref "FLASH") (pin "1") (pinfunction "1_1") (pintype "passive"))
      (node (ref "FLASH") (pin "2") (pinfunction "2_2") (pintype "passive"))
      (node (ref "POWER") (pin "14") (pinfunction "14_14") (pintype "passive"))
      (node (ref "Q4") (pin "1") (pinfunction "G_1") (pintype "bidirectional"))
      (node (ref "R16") (pin "2") (pinfunction "2_2") (pintype "passive"))
      (node (ref "R18") (pin "2") (pinfunction "2_2") (pintype "passive"))
      (node (ref "R20") (pin "2") (pinfunction "2_2") (pintype "passive"))
      (node (ref "R22") (pin "2") (pinfunction "2_2") (pintype "passive"))
      (node (ref "R23") (pin "1") (pinfunction "1_1") (pintype "passive"))
      (node (ref "R27") (pin "2") (pinfunction "2_2") (pintype "passive"))
      (node (ref "R29") (pin "2") (pinfunction "2_2") (pintype "passive"))
      (node (ref "R31") (pin "2") (pinfunction "2_2") (pintype "passive"))
      (node (ref "R33") (pin "2") (pinfunction "2_2") (pintype "passive"))
      (node (ref "R34") (pin "2") (pinfunction "2_2") (pintype "passive"))
      (node (ref "R36") (pin "1") (pinfunction "1_1") (pintype "passive"))
      (node (ref "R37") (pin "2") (pinfunction "2_2") (pintype "passive"))
      (node (ref "R39") (pin "2") (pinfunction "2_2") (pintype "passive"))
      (node (ref "R42") (pin "2") (pinfunction "2_2") (pintype "passive"))
      (node (ref "R46") (pin "2") (pinfunction "2_2") (pintype "passive"))
      (node (ref "R49") (pin "2") (pinfunction "2_2") (pintype "passive"))
      (node (ref "R51") (pin "2") (pinfunction "2_2") (pintype "passive"))
      (node (ref "R53") (pin "2") (pinfunction "2_2") (pintype "passive"))
      (node (ref "R54") (pin "2") (pinfunction "2_2") (pintype "passive"))
      (node (ref "R55") (pin "2") (pinfunction "2_2") (pintype "passive"))
      (node (ref "R56") (pin "2") (pinfunction "2_2") (pintype "passive"))
      (node (ref "U$5") (pin "P$12") (pinfunction "3.3V_P$12") (pintype "bidirectional"))
      (node (ref "USB-UART_1") (pin "3") (pinfunction "3_3") (pintype "passive"))
    )
    (net (code "217") (name "VDD_5V") (class "Default")
      (node (ref "Q8") (pin "1") (pinfunction "G_1") (pintype "bidirectional"))
      (node (ref "R35") (pin "1") (pinfunction "1_1") (pintype "passive"))
      (node (ref "USB-UART_2") (pin "2") (pinfunction "2_2") (pintype "passive"))
      (node (ref "VCCQ") (pin "1") (pinfunction "1_1") (pintype "passive"))
      (node (ref "VDD") (pin "1") (pinfunction "1_1") (pintype "passive"))
      (node (ref "VDDH") (pin "1") (pinfunction "1_1") (pintype "passive"))
      (node (ref "VDDLS") (pin "1") (pinfunction "1_1") (pintype "passive"))
      (node (ref "VDD_3V3") (pin "1") (pinfunction "1_1") (pintype "passive"))
      (node (ref "VDD_CORE") (pin "1") (pinfunction "1_1") (pintype "passive"))
    )
    (net (code "218") (name "unconnected-(ALL_JTAG-Pad11)") (class "Default")
      (node (ref "ALL_JTAG") (pin "11") (pinfunction "11_11") (pintype "passive"))
    )
    (net (code "219") (name "unconnected-(ALL_JTAG-Pad15)") (class "Default")
      (node (ref "ALL_JTAG") (pin "15") (pinfunction "15_15") (pintype "passive"))
    )
    (net (code "220") (name "unconnected-(ALL_JTAG-Pad17)") (class "Default")
      (node (ref "ALL_JTAG") (pin "17") (pinfunction "17_17") (pintype "passive"))
    )
    (net (code "221") (name "unconnected-(ALL_JTAG-Pad19)") (class "Default")
      (node (ref "ALL_JTAG") (pin "19") (pinfunction "19_19") (pintype "passive"))
    )
    (net (code "222") (name "unconnected-(FLASH-Pad5)") (class "Default")
      (node (ref "FLASH") (pin "5") (pinfunction "5_5") (pintype "passive"))
    )
    (net (code "223") (name "unconnected-(FLASH-Pad7)") (class "Default")
      (node (ref "FLASH") (pin "7") (pinfunction "7_7") (pintype "passive"))
    )
    (net (code "224") (name "unconnected-(FLASH-Pad9)") (class "Default")
      (node (ref "FLASH") (pin "9") (pinfunction "9_9") (pintype "passive"))
    )
    (net (code "225") (name "unconnected-(FLASH-Pad11)") (class "Default")
      (node (ref "FLASH") (pin "11") (pinfunction "11_11") (pintype "passive"))
    )
    (net (code "226") (name "unconnected-(IC12-N.C.-Pad1)") (class "Default")
      (node (ref "IC12") (pin "1") (pinfunction "N.C._1") (pintype "no_connect"))
    )
    (net (code "227") (name "unconnected-(IC13-N.C.-Pad1)") (class "Default")
      (node (ref "IC13") (pin "1") (pinfunction "N.C._1") (pintype "no_connect"))
    )
    (net (code "228") (name "unconnected-(SPI_1-Pad1)") (class "Default")
      (node (ref "SPI_1") (pin "1") (pinfunction "1_1") (pintype "passive"))
    )
    (net (code "229") (name "unconnected-(SPI_1-Pad2)") (class "Default")
      (node (ref "SPI_1") (pin "2") (pinfunction "2_2") (pintype "passive"))
    )
    (net (code "230") (name "unconnected-(SPI_1-Pad3)") (class "Default")
      (node (ref "SPI_1") (pin "3") (pinfunction "3_3") (pintype "passive"))
    )
    (net (code "231") (name "unconnected-(SPI_1-Pad4)") (class "Default")
      (node (ref "SPI_1") (pin "4") (pinfunction "4_4") (pintype "passive"))
    )
    (net (code "232") (name "unconnected-(SPI_1-Pad5)") (class "Default")
      (node (ref "SPI_1") (pin "5") (pinfunction "5_5") (pintype "passive"))
    )
    (net (code "233") (name "unconnected-(SPI_1-Pad6)") (class "Default")
      (node (ref "SPI_1") (pin "6") (pinfunction "6_6") (pintype "passive"))
    )
    (net (code "234") (name "unconnected-(SPI_1-Pad7)") (class "Default")
      (node (ref "SPI_1") (pin "7") (pinfunction "7_7") (pintype "passive"))
    )
    (net (code "235") (name "unconnected-(SPI_1-Pad8)") (class "Default")
      (node (ref "SPI_1") (pin "8") (pinfunction "8_8") (pintype "passive"))
    )
    (net (code "236") (name "unconnected-(SPI_1-Pad9)") (class "Default")
      (node (ref "SPI_1") (pin "9") (pinfunction "9_9") (pintype "passive"))
    )
    (net (code "237") (name "unconnected-(SPI_1-Pad10)") (class "Default")
      (node (ref "SPI_1") (pin "10") (pinfunction "10_10") (pintype "passive"))
    )
    (net (code "238") (name "unconnected-(SPI_2-Pad5)") (class "Default")
      (node (ref "SPI_2") (pin "5") (pinfunction "5_5") (pintype "passive"))
    )
    (net (code "239") (name "unconnected-(SPI_2-Pad6)") (class "Default")
      (node (ref "SPI_2") (pin "6") (pinfunction "6_6") (pintype "passive"))
    )
    (net (code "240") (name "unconnected-(SPI_2-Pad7)") (class "Default")
      (node (ref "SPI_2") (pin "7") (pinfunction "7_7") (pintype "passive"))
    )
    (net (code "241") (name "unconnected-(SPI_2-Pad8)") (class "Default")
      (node (ref "SPI_2") (pin "8") (pinfunction "8_8") (pintype "passive"))
    )
    (net (code "242") (name "unconnected-(SPI_2-Pad9)") (class "Default")
      (node (ref "SPI_2") (pin "9") (pinfunction "9_9") (pintype "passive"))
    )
    (net (code "243") (name "unconnected-(U$1-Pad2)") (class "Default")
      (node (ref "U$1") (pin "2") (pinfunction "2_2") (pintype "bidirectional"))
    )
    (net (code "244") (name "unconnected-(U$1-Pad41)") (class "Default")
      (node (ref "U$1") (pin "41") (pinfunction "41_41") (pintype "bidirectional"))
    )
    (net (code "245") (name "unconnected-(U$2-Pad2)") (class "Default")
      (node (ref "U$2") (pin "2") (pinfunction "2_2") (pintype "bidirectional"))
    )
    (net (code "246") (name "unconnected-(U$2-Pad41)") (class "Default")
      (node (ref "U$2") (pin "41") (pinfunction "41_41") (pintype "bidirectional"))
    )
    (net (code "247") (name "unconnected-(U$3-Pad2)") (class "Default")
      (node (ref "U$3") (pin "2") (pinfunction "2_2") (pintype "bidirectional"))
    )
    (net (code "248") (name "unconnected-(U$3-Pad41)") (class "Default")
      (node (ref "U$3") (pin "41") (pinfunction "41_41") (pintype "bidirectional"))
    )
    (net (code "249") (name "unconnected-(U$4-Pad2)") (class "Default")
      (node (ref "U$4") (pin "2") (pinfunction "2_2") (pintype "bidirectional"))
    )
    (net (code "250") (name "unconnected-(U$4-Pad41)") (class "Default")
      (node (ref "U$4") (pin "41") (pinfunction "41_41") (pintype "bidirectional"))
    )
    (net (code "251") (name "unconnected-(U$5-ANT-PadP$16)") (class "Default")
      (node (ref "U$5") (pin "P$16") (pinfunction "ANT_P$16") (pintype "bidirectional"))
    )
    (net (code "252") (name "unconnected-(U$5-DIO0-PadP$11)") (class "Default")
      (node (ref "U$5") (pin "P$11") (pinfunction "DIO0_P$11") (pintype "bidirectional"))
    )
    (net (code "253") (name "unconnected-(U$5-DIO1-PadP$10)") (class "Default")
      (node (ref "U$5") (pin "P$10") (pinfunction "DIO1_P$10") (pintype "bidirectional"))
    )
    (net (code "254") (name "unconnected-(U$5-DIO2-PadP$9)") (class "Default")
      (node (ref "U$5") (pin "P$9") (pinfunction "DIO2_P$9") (pintype "bidirectional"))
    )
    (net (code "255") (name "unconnected-(U$5-DIO3-PadP$14)") (class "Default")
      (node (ref "U$5") (pin "P$14") (pinfunction "DIO3_P$14") (pintype "bidirectional"))
    )
    (net (code "256") (name "unconnected-(U$5-DIO4-PadP$13)") (class "Default")
      (node (ref "U$5") (pin "P$13") (pinfunction "DIO4_P$13") (pintype "bidirectional"))
    )
    (net (code "257") (name "unconnected-(U$5-DIO5-PadP$7)") (class "Default")
      (node (ref "U$5") (pin "P$7") (pinfunction "DIO5_P$7") (pintype "bidirectional"))
    )
    (net (code "258") (name "unconnected-(U$5-RESET-PadP$6)") (class "Default")
      (node (ref "U$5") (pin "P$6") (pinfunction "RESET_P$6") (pintype "bidirectional"))
    )
    (net (code "259") (name "unconnected-(USB-UART_2-Pad1)") (class "Default")
      (node (ref "USB-UART_2") (pin "1") (pinfunction "1_1") (pintype "passive"))
    )
    (net (code "260") (name "unconnected-(USB-UART_2-Pad3)") (class "Default")
      (node (ref "USB-UART_2") (pin "3") (pinfunction "3_3") (pintype "passive"))
    )
    (net (code "261") (name "unconnected-(USB-UART_2-Pad4)") (class "Default")
      (node (ref "USB-UART_2") (pin "4") (pinfunction "4_4") (pintype "passive"))
    )
  )
)
